# ST-BOARD-1-02.net
KiCad netlist of a schematic drawn in EAGLE
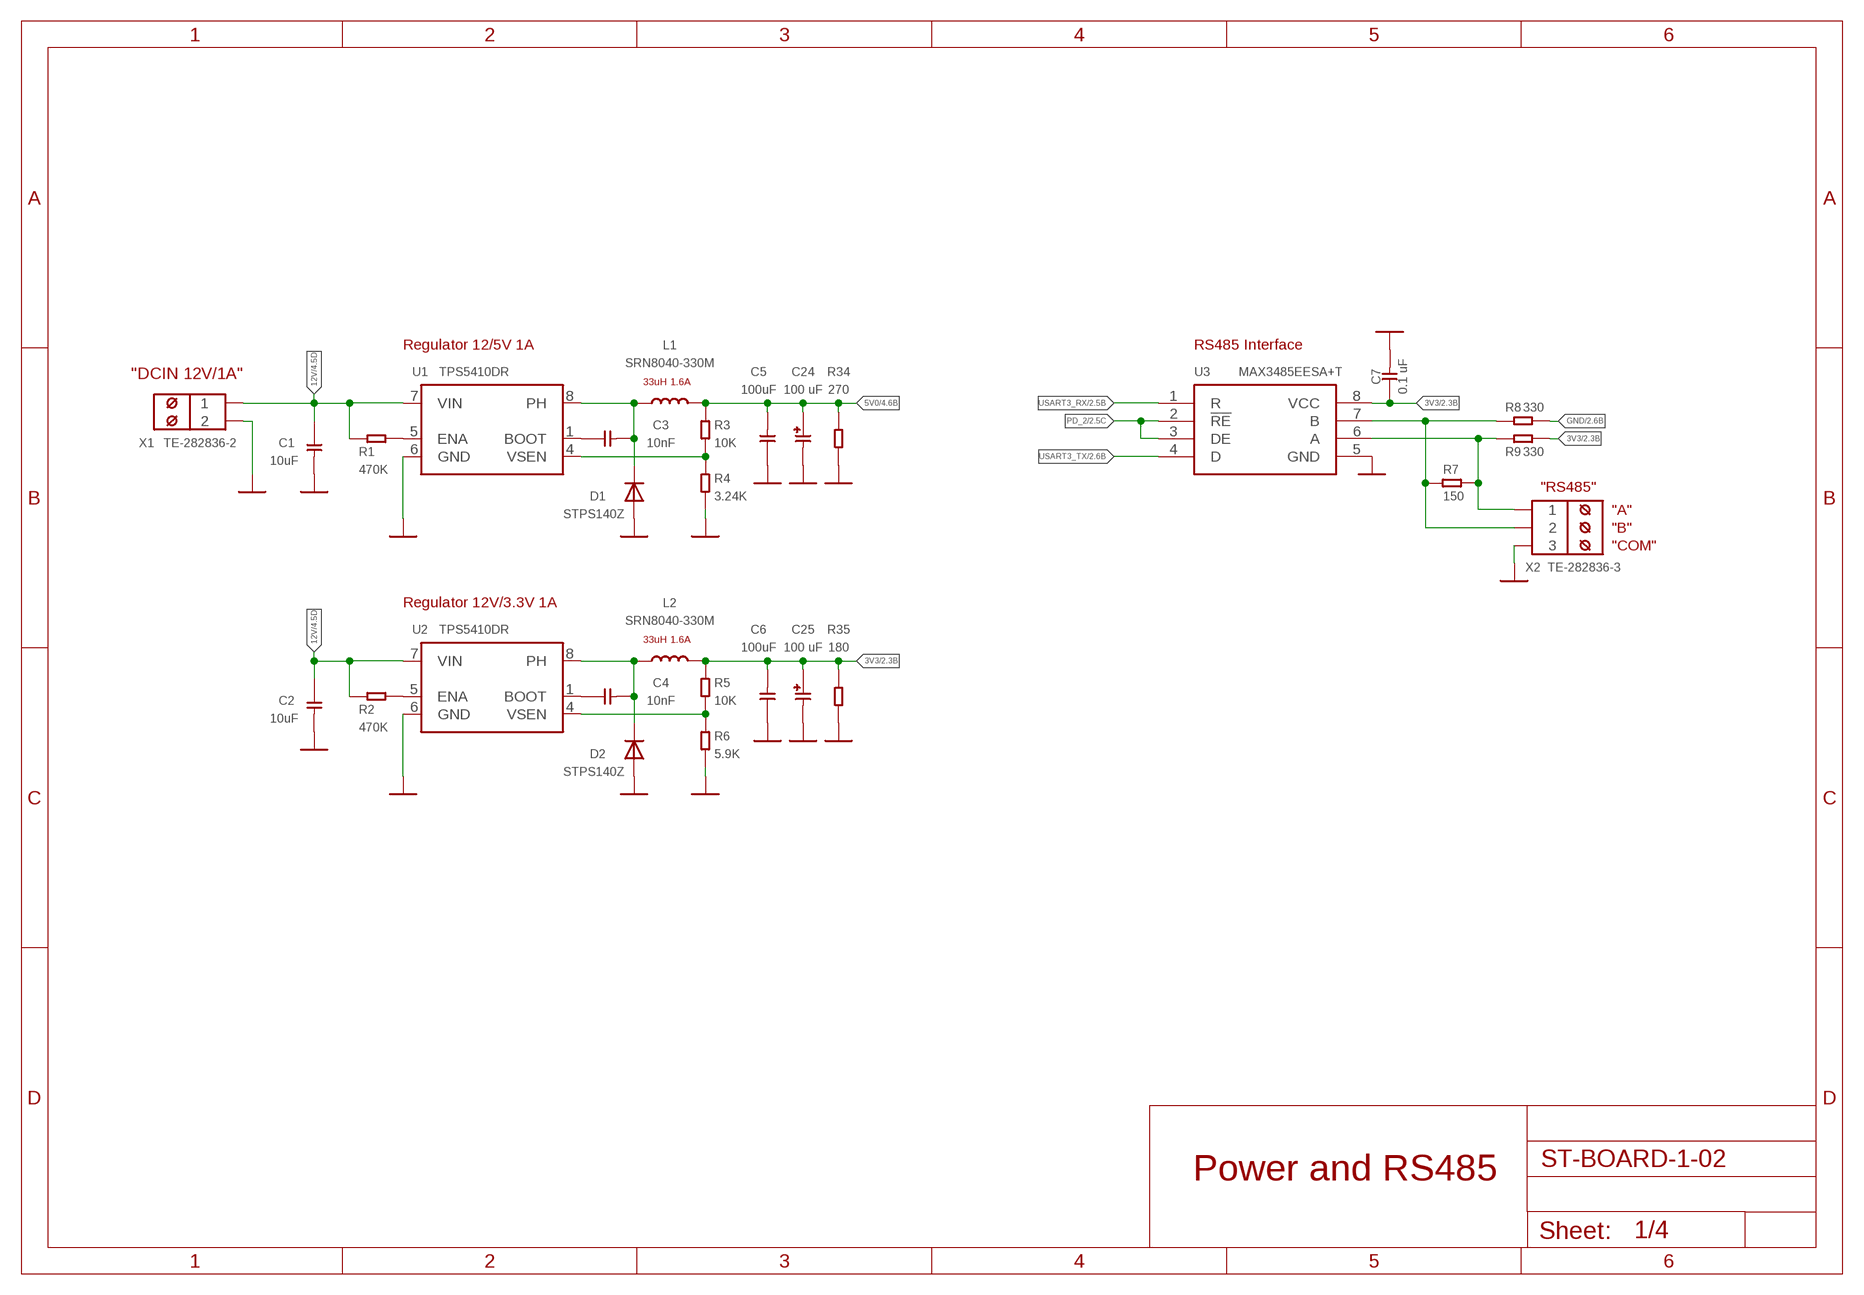
[diagram p0: schematic, sheet 1]
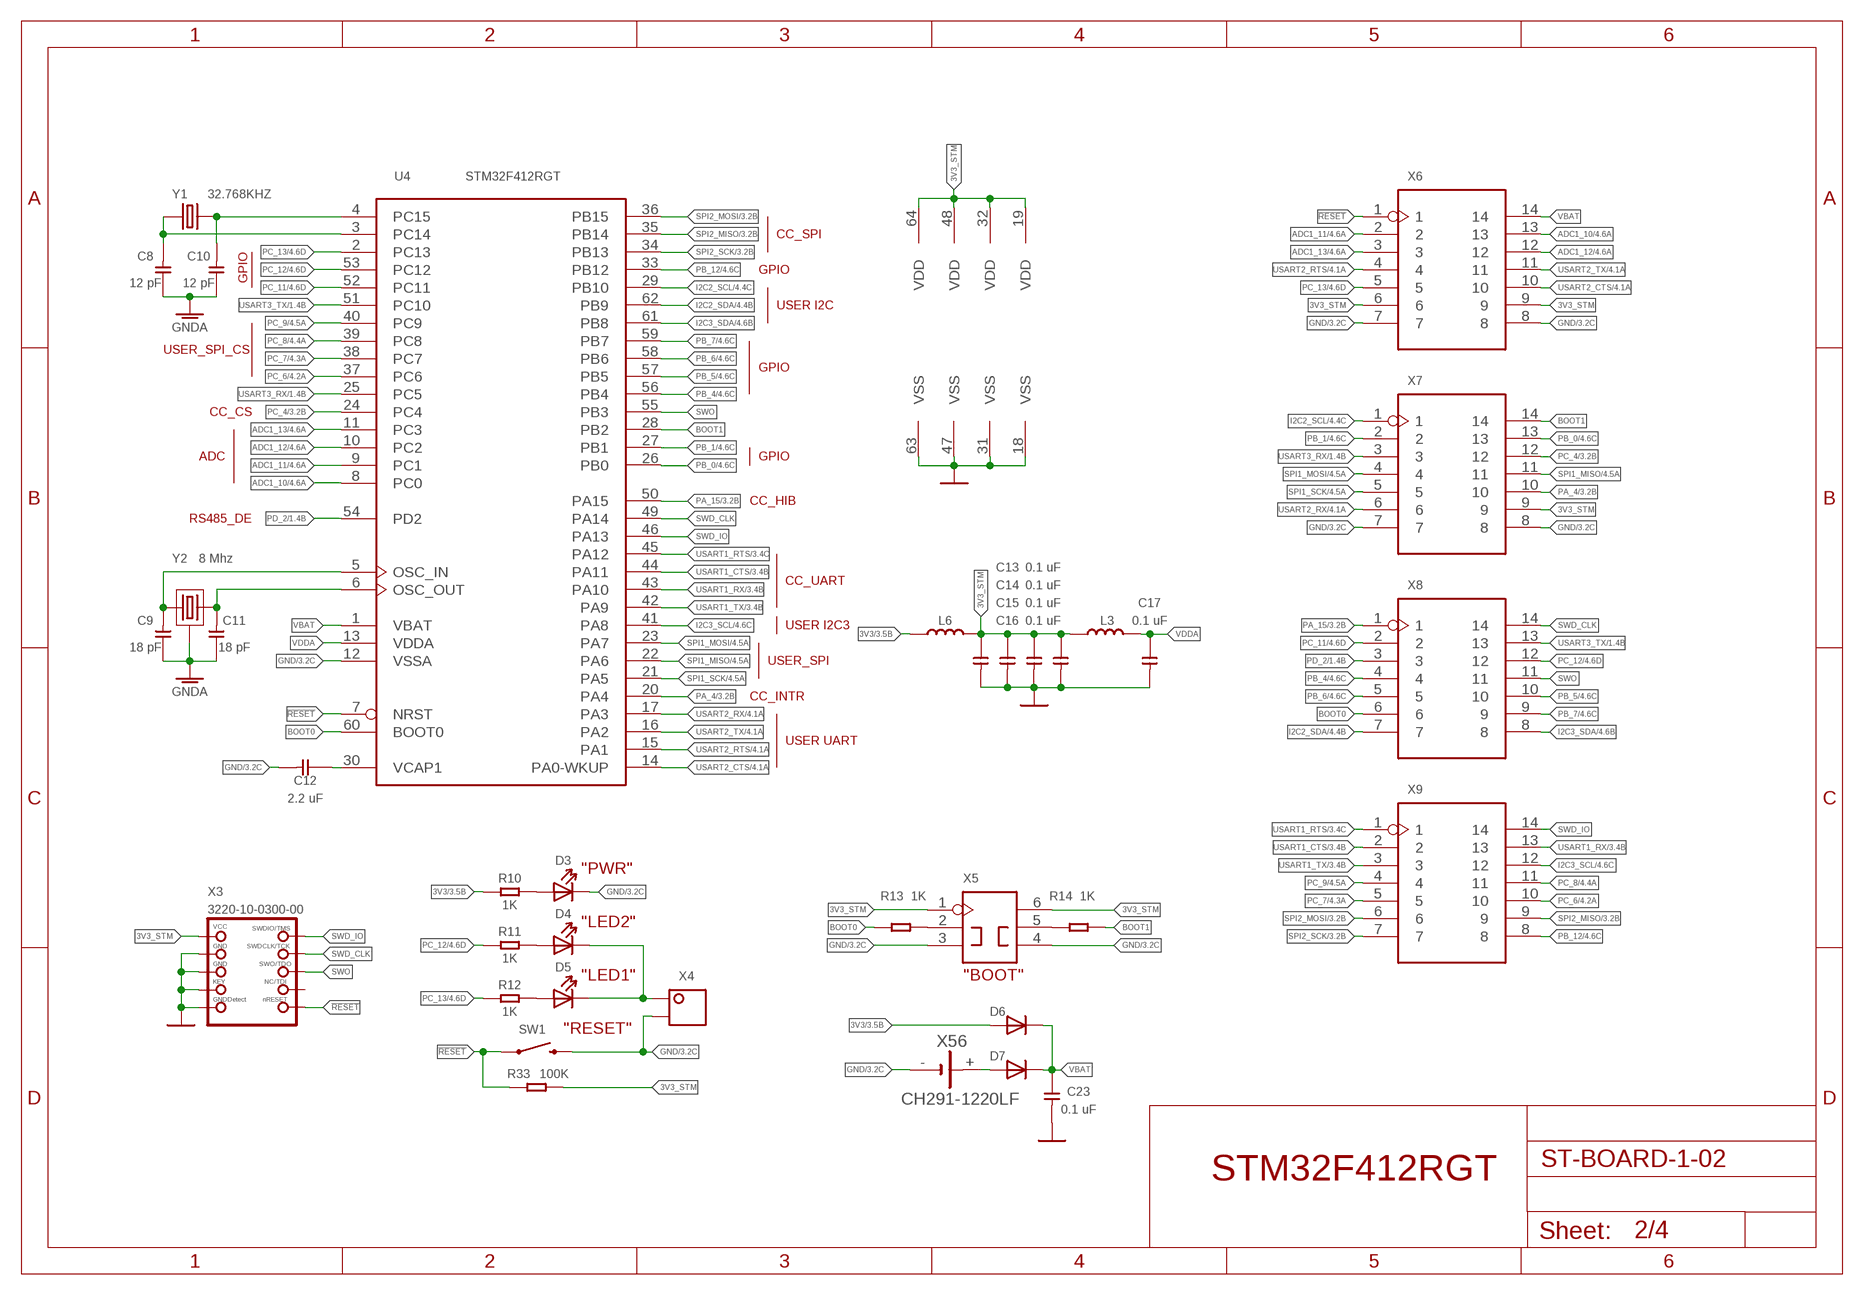
[diagram p1: schematic, sheet 2]
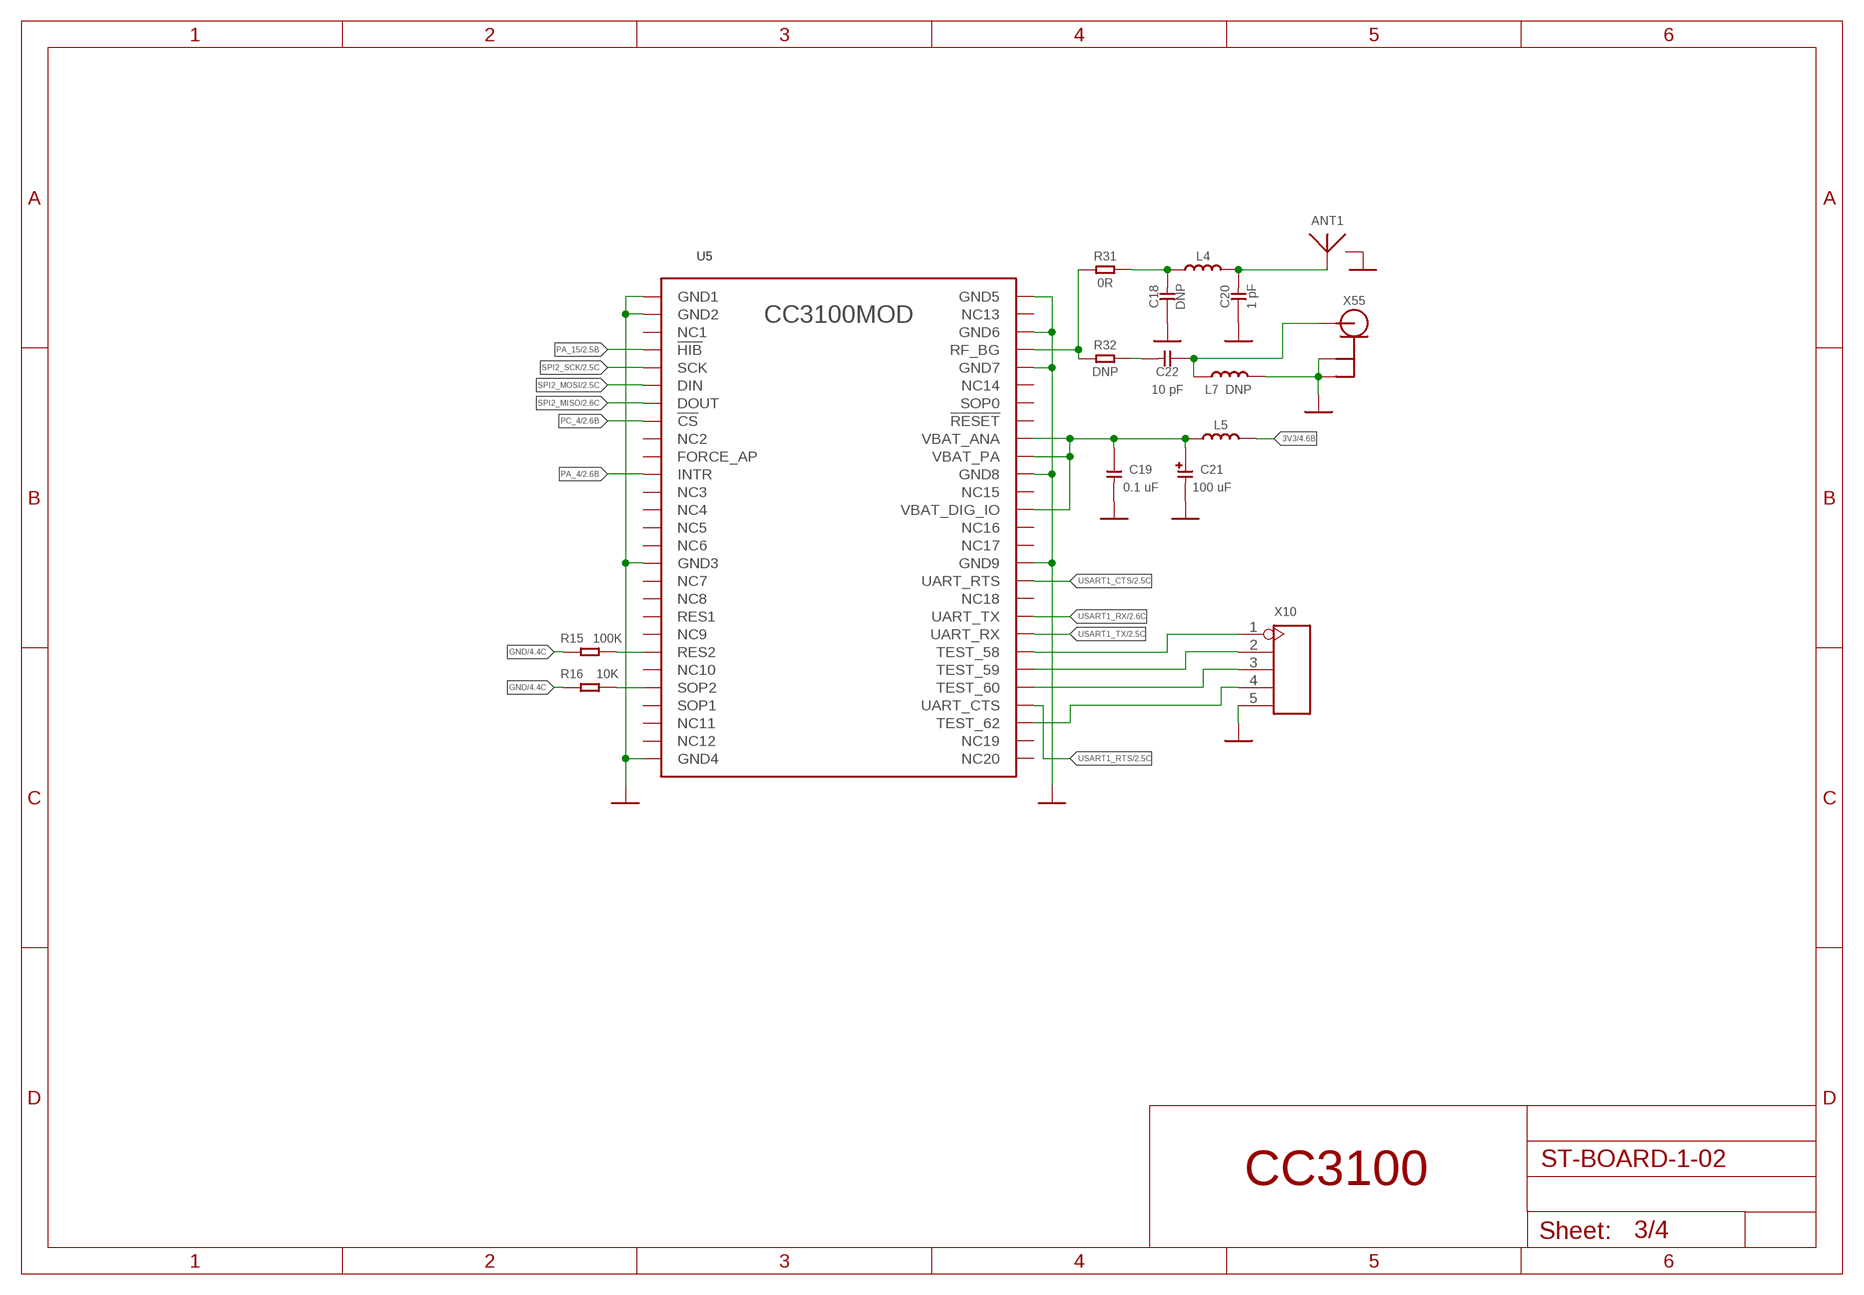
[diagram p2: schematic, sheet 3]
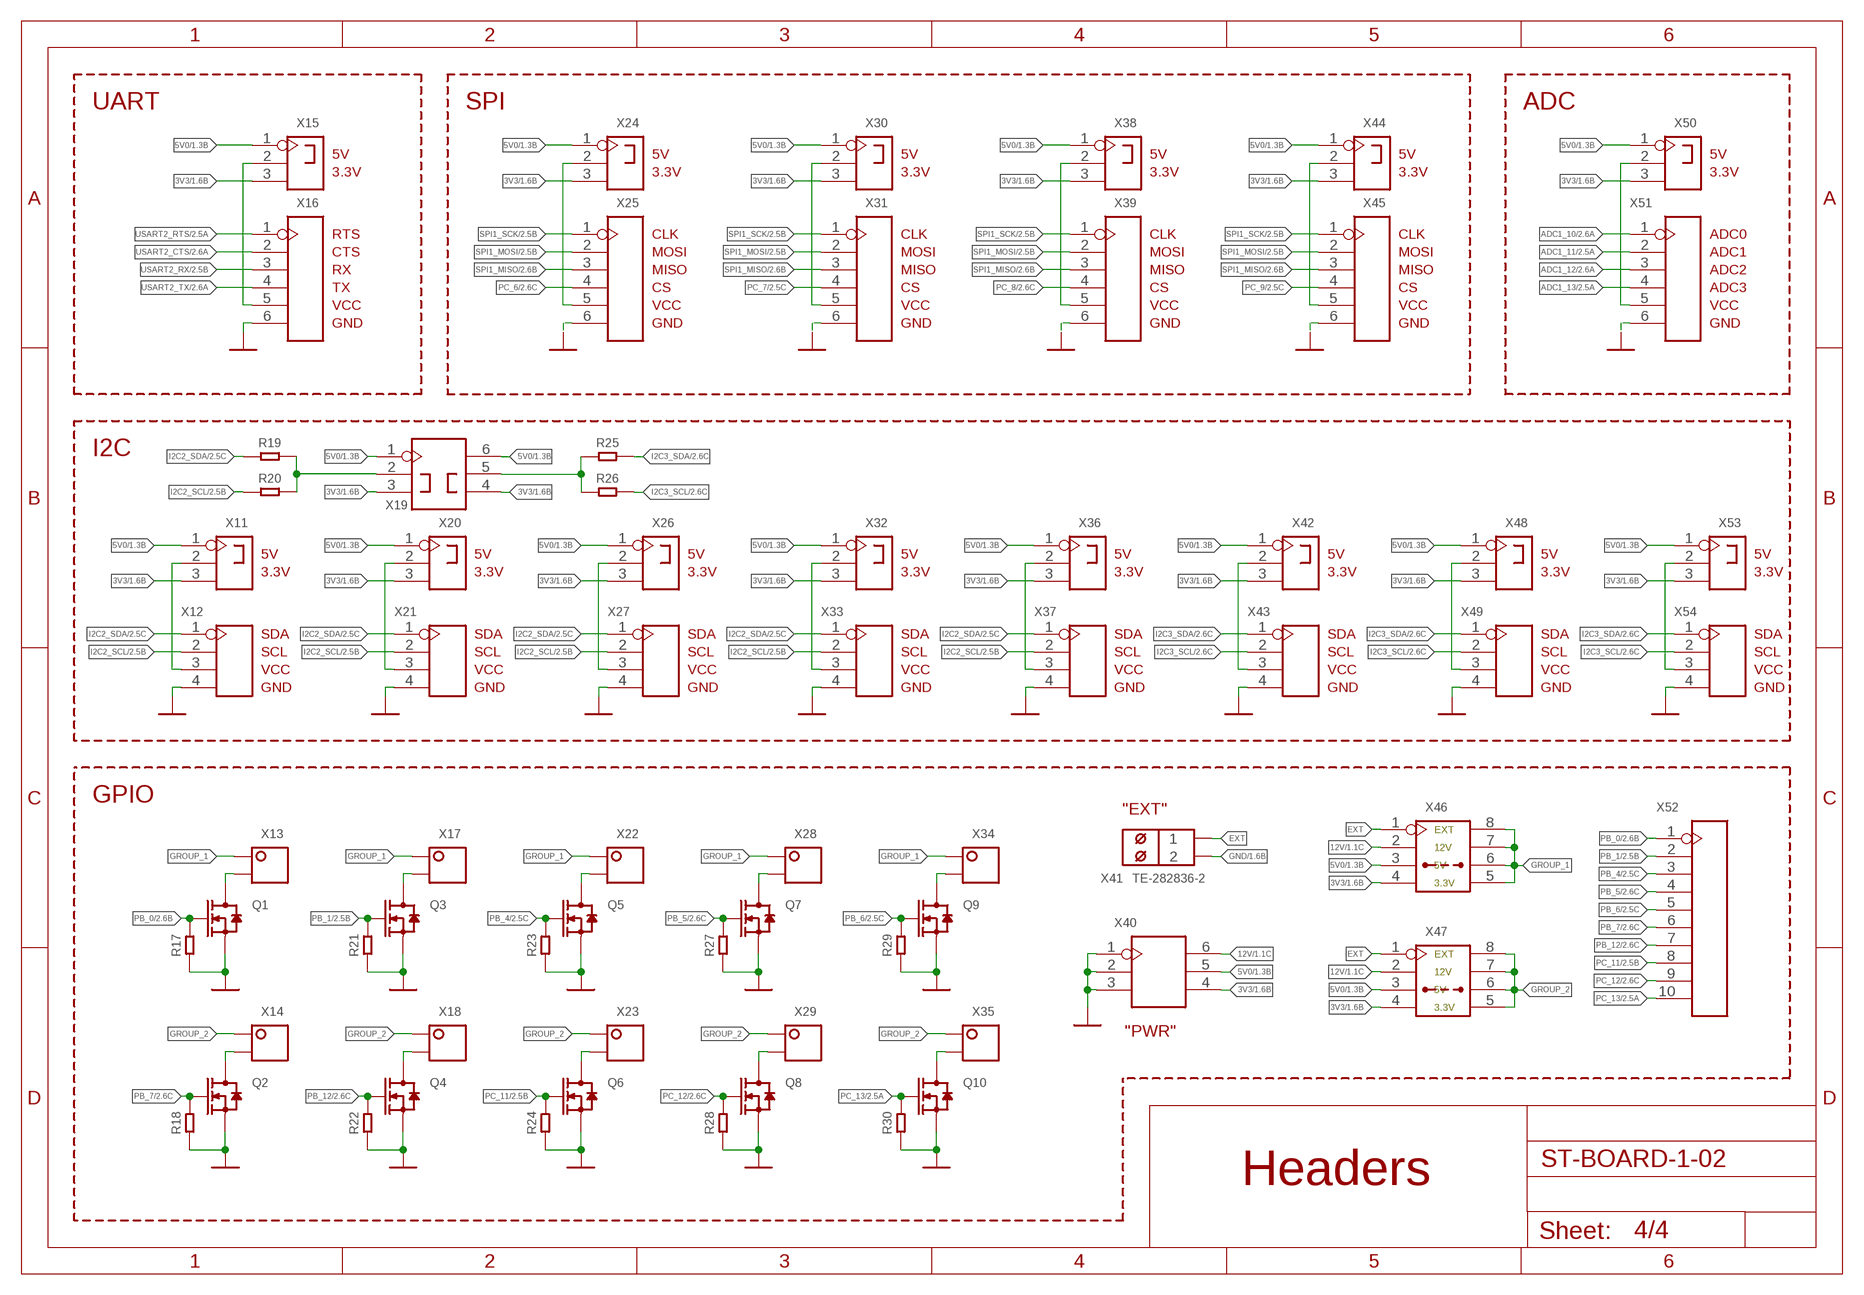
[diagram p3: schematic, sheet 4]

(export (version "E")
  (design (tool "Eeschema 10.0.6"))
  (components
    (comp (ref "Q1")
      (value "MOSFET-N-(SOT-23)")
      (footprint "eagle-import:SOT-23")
      (libsource (lib "eagle-import") (part "MOSFET-N-(SOT-23)"))
    )
    (comp (ref "Q2")
      (value "MOSFET-N-(SOT-23)")
      (footprint "eagle-import:SOT-23")
      (libsource (lib "eagle-import") (part "MOSFET-N-(SOT-23)"))
    )
    (comp (ref "Q3")
      (value "MOSFET-N-(SOT-23)")
      (footprint "eagle-import:SOT-23")
      (libsource (lib "eagle-import") (part "MOSFET-N-(SOT-23)"))
    )
    (comp (ref "Q4")
      (value "MOSFET-N-(SOT-23)")
      (footprint "eagle-import:SOT-23")
      (libsource (lib "eagle-import") (part "MOSFET-N-(SOT-23)"))
    )
    (comp (ref "Q5")
      (value "MOSFET-N-(SOT-23)")
      (footprint "eagle-import:SOT-23")
      (libsource (lib "eagle-import") (part "MOSFET-N-(SOT-23)"))
    )
    (comp (ref "Q6")
      (value "MOSFET-N-(SOT-23)")
      (footprint "eagle-import:SOT-23")
      (libsource (lib "eagle-import") (part "MOSFET-N-(SOT-23)"))
    )
    (comp (ref "Q7")
      (value "MOSFET-N-(SOT-23)")
      (footprint "eagle-import:SOT-23")
      (libsource (lib "eagle-import") (part "MOSFET-N-(SOT-23)"))
    )
    (comp (ref "Q8")
      (value "MOSFET-N-(SOT-23)")
      (footprint "eagle-import:SOT-23")
      (libsource (lib "eagle-import") (part "MOSFET-N-(SOT-23)"))
    )
    (comp (ref "Q9")
      (value "MOSFET-N-(SOT-23)")
      (footprint "eagle-import:SOT-23")
      (libsource (lib "eagle-import") (part "MOSFET-N-(SOT-23)"))
    )
    (comp (ref "Q10")
      (value "MOSFET-N-(SOT-23)")
      (footprint "eagle-import:SOT-23")
      (libsource (lib "eagle-import") (part "MOSFET-N-(SOT-23)"))
    )
    (comp (ref "R17")
      (value "CHIP-RESISTOR-0603")
      (footprint "eagle-import:R0603")
      (libsource (lib "eagle-import") (part "CHIP-RESISTOR-0603"))
    )
    (comp (ref "R18")
      (value "CHIP-RESISTOR-0603")
      (footprint "eagle-import:R0603")
      (libsource (lib "eagle-import") (part "CHIP-RESISTOR-0603"))
    )
    (comp (ref "R19")
      (value "CHIP-RESISTOR-0603")
      (footprint "eagle-import:R0603")
      (libsource (lib "eagle-import") (part "CHIP-RESISTOR-0603"))
    )
    (comp (ref "R20")
      (value "CHIP-RESISTOR-0603")
      (footprint "eagle-import:R0603")
      (libsource (lib "eagle-import") (part "CHIP-RESISTOR-0603"))
    )
    (comp (ref "R21")
      (value "CHIP-RESISTOR-0603")
      (footprint "eagle-import:R0603")
      (libsource (lib "eagle-import") (part "CHIP-RESISTOR-0603"))
    )
    (comp (ref "R22")
      (value "CHIP-RESISTOR-0603")
      (footprint "eagle-import:R0603")
      (libsource (lib "eagle-import") (part "CHIP-RESISTOR-0603"))
    )
    (comp (ref "R23")
      (value "CHIP-RESISTOR-0603")
      (footprint "eagle-import:R0603")
      (libsource (lib "eagle-import") (part "CHIP-RESISTOR-0603"))
    )
    (comp (ref "R24")
      (value "CHIP-RESISTOR-0603")
      (footprint "eagle-import:R0603")
      (libsource (lib "eagle-import") (part "CHIP-RESISTOR-0603"))
    )
    (comp (ref "R25")
      (value "CHIP-RESISTOR-0603")
      (footprint "eagle-import:R0603")
      (libsource (lib "eagle-import") (part "CHIP-RESISTOR-0603"))
    )
    (comp (ref "R26")
      (value "CHIP-RESISTOR-0603")
      (footprint "eagle-import:R0603")
      (libsource (lib "eagle-import") (part "CHIP-RESISTOR-0603"))
    )
    (comp (ref "R27")
      (value "CHIP-RESISTOR-0603")
      (footprint "eagle-import:R0603")
      (libsource (lib "eagle-import") (part "CHIP-RESISTOR-0603"))
    )
    (comp (ref "R28")
      (value "CHIP-RESISTOR-0603")
      (footprint "eagle-import:R0603")
      (libsource (lib "eagle-import") (part "CHIP-RESISTOR-0603"))
    )
    (comp (ref "R29")
      (value "CHIP-RESISTOR-0603")
      (footprint "eagle-import:R0603")
      (libsource (lib "eagle-import") (part "CHIP-RESISTOR-0603"))
    )
    (comp (ref "R30")
      (value "CHIP-RESISTOR-0603")
      (footprint "eagle-import:R0603")
      (libsource (lib "eagle-import") (part "CHIP-RESISTOR-0603"))
    )
    (comp (ref "X11")
      (value "3p-2.54")
      (footprint "eagle-import:H3-2.54")
      (fields (field (name "MPN") "F185-1103A0BSYA1"))
      (libsource (lib "eagle-import") (part "DIP-HEADER-VERT(3P-2.54)_M"))
    )
    (comp (ref "X12")
      (value "DIP-HEADER-VERT(4P-2.54)_WF")
      (footprint "eagle-import:22-23-2041")
      (libsource (lib "eagle-import") (part "DIP-HEADER-VERT(4P-2.54)_WF"))
    )
    (comp (ref "X13")
      (value "2p-2.54")
      (footprint "eagle-import:22-23-2021")
      (libsource (lib "eagle-import") (part "DIP-HEADER-VERT(2P-2.54)_WF"))
    )
    (comp (ref "X14")
      (value "2p-2.54")
      (footprint "eagle-import:22-23-2021")
      (libsource (lib "eagle-import") (part "DIP-HEADER-VERT(2P-2.54)_WF"))
    )
    (comp (ref "X15")
      (value "3p-2.54")
      (footprint "eagle-import:H3-2.54")
      (fields (field (name "MPN") "F185-1103A0BSYA1"))
      (libsource (lib "eagle-import") (part "DIP-HEADER-VERT(3P-2.54)_M"))
    )
    (comp (ref "X16")
      (value "DIP-HEADER-VERT(6P-2.54)_WF")
      (footprint "eagle-import:22-23-2061")
      (libsource (lib "eagle-import") (part "DIP-HEADER-VERT(6P-2.54)_WF"))
    )
    (comp (ref "X17")
      (value "2p-2.54")
      (footprint "eagle-import:22-23-2021")
      (libsource (lib "eagle-import") (part "DIP-HEADER-VERT(2P-2.54)_WF"))
    )
    (comp (ref "X18")
      (value "2p-2.54")
      (footprint "eagle-import:22-23-2021")
      (libsource (lib "eagle-import") (part "DIP-HEADER-VERT(2P-2.54)_WF"))
    )
    (comp (ref "X19")
      (value "2x3p-2.54")
      (footprint "eagle-import:H2X3-2.54")
      (fields (field (name "MPN") "P125-12A1BS116A1"))
      (libsource (lib "eagle-import") (part "DIP-HEADER-VERT(2X3P-2.54）-2.54"))
    )
    (comp (ref "X20")
      (value "3p-2.54")
      (footprint "eagle-import:H3-2.54")
      (fields (field (name "MPN") "F185-1103A0BSYA1"))
      (libsource (lib "eagle-import") (part "DIP-HEADER-VERT(3P-2.54)_M"))
    )
    (comp (ref "X21")
      (value "DIP-HEADER-VERT(4P-2.54)_WF")
      (footprint "eagle-import:22-23-2041")
      (libsource (lib "eagle-import") (part "DIP-HEADER-VERT(4P-2.54)_WF"))
    )
    (comp (ref "X22")
      (value "2p-2.54")
      (footprint "eagle-import:22-23-2021")
      (libsource (lib "eagle-import") (part "DIP-HEADER-VERT(2P-2.54)_WF"))
    )
    (comp (ref "X23")
      (value "2p-2.54")
      (footprint "eagle-import:22-23-2021")
      (libsource (lib "eagle-import") (part "DIP-HEADER-VERT(2P-2.54)_WF"))
    )
    (comp (ref "X24")
      (value "3p-2.54")
      (footprint "eagle-import:H3-2.54")
      (fields (field (name "MPN") "F185-1103A0BSYA1"))
      (libsource (lib "eagle-import") (part "DIP-HEADER-VERT(3P-2.54)_M"))
    )
    (comp (ref "X25")
      (value "DIP-HEADER-VERT(6P-2.54)_WF")
      (footprint "eagle-import:22-23-2061")
      (libsource (lib "eagle-import") (part "DIP-HEADER-VERT(6P-2.54)_WF"))
    )
    (comp (ref "X26")
      (value "3p-2.54")
      (footprint "eagle-import:H3-2.54")
      (fields (field (name "MPN") "F185-1103A0BSYA1"))
      (libsource (lib "eagle-import") (part "DIP-HEADER-VERT(3P-2.54)_M"))
    )
    (comp (ref "X27")
      (value "DIP-HEADER-VERT(4P-2.54)_WF")
      (footprint "eagle-import:22-23-2041")
      (libsource (lib "eagle-import") (part "DIP-HEADER-VERT(4P-2.54)_WF"))
    )
    (comp (ref "X28")
      (value "2p-2.54")
      (footprint "eagle-import:22-23-2021")
      (libsource (lib "eagle-import") (part "DIP-HEADER-VERT(2P-2.54)_WF"))
    )
    (comp (ref "X29")
      (value "2p-2.54")
      (footprint "eagle-import:22-23-2021")
      (libsource (lib "eagle-import") (part "DIP-HEADER-VERT(2P-2.54)_WF"))
    )
    (comp (ref "X30")
      (value "3p-2.54")
      (footprint "eagle-import:H3-2.54")
      (fields (field (name "MPN") "F185-1103A0BSYA1"))
      (libsource (lib "eagle-import") (part "DIP-HEADER-VERT(3P-2.54)_M"))
    )
    (comp (ref "X31")
      (value "DIP-HEADER-VERT(6P-2.54)_WF")
      (footprint "eagle-import:22-23-2061")
      (libsource (lib "eagle-import") (part "DIP-HEADER-VERT(6P-2.54)_WF"))
    )
    (comp (ref "X32")
      (value "3p-2.54")
      (footprint "eagle-import:H3-2.54")
      (fields (field (name "MPN") "F185-1103A0BSYA1"))
      (libsource (lib "eagle-import") (part "DIP-HEADER-VERT(3P-2.54)_M"))
    )
    (comp (ref "X33")
      (value "DIP-HEADER-VERT(4P-2.54)_WF")
      (footprint "eagle-import:22-23-2041")
      (libsource (lib "eagle-import") (part "DIP-HEADER-VERT(4P-2.54)_WF"))
    )
    (comp (ref "X34")
      (value "2p-2.54")
      (footprint "eagle-import:22-23-2021")
      (libsource (lib "eagle-import") (part "DIP-HEADER-VERT(2P-2.54)_WF"))
    )
    (comp (ref "X35")
      (value "2p-2.54")
      (footprint "eagle-import:22-23-2021")
      (libsource (lib "eagle-import") (part "DIP-HEADER-VERT(2P-2.54)_WF"))
    )
    (comp (ref "X36")
      (value "3p-2.54")
      (footprint "eagle-import:H3-2.54")
      (fields (field (name "MPN") "F185-1103A0BSYA1"))
      (libsource (lib "eagle-import") (part "DIP-HEADER-VERT(3P-2.54)_M"))
    )
    (comp (ref "X37")
      (value "DIP-HEADER-VERT(4P-2.54)_WF")
      (footprint "eagle-import:22-23-2041")
      (libsource (lib "eagle-import") (part "DIP-HEADER-VERT(4P-2.54)_WF"))
    )
    (comp (ref "X38")
      (value "3p-2.54")
      (footprint "eagle-import:H3-2.54")
      (fields (field (name "MPN") "F185-1103A0BSYA1"))
      (libsource (lib "eagle-import") (part "DIP-HEADER-VERT(3P-2.54)_M"))
    )
    (comp (ref "X39")
      (value "DIP-HEADER-VERT(6P-2.54)_WF")
      (footprint "eagle-import:22-23-2061")
      (libsource (lib "eagle-import") (part "DIP-HEADER-VERT(6P-2.54)_WF"))
    )
    (comp (ref "X40")
      (value "2x3p-2.54")
      (footprint "eagle-import:H2X3-2.54")
      (fields (field (name "MPN") "P125-12A1BS116A1"))
      (libsource (lib "eagle-import") (part "DIP-HEADER-VERT(2X3P-2.54）-2.54"))
    )
    (comp (ref "X41")
      (value "TE-282836-2")
      (footprint "eagle-import:W237-102")
      (libsource (lib "eagle-import") (part "TE-282836-2"))
    )
    (comp (ref "X42")
      (value "3p-2.54")
      (footprint "eagle-import:H3-2.54")
      (fields (field (name "MPN") "F185-1103A0BSYA1"))
      (libsource (lib "eagle-import") (part "DIP-HEADER-VERT(3P-2.54)_M"))
    )
    (comp (ref "X43")
      (value "DIP-HEADER-VERT(4P-2.54)_WF")
      (footprint "eagle-import:22-23-2041")
      (libsource (lib "eagle-import") (part "DIP-HEADER-VERT(4P-2.54)_WF"))
    )
    (comp (ref "X44")
      (value "3p-2.54")
      (footprint "eagle-import:H3-2.54")
      (fields (field (name "MPN") "F185-1103A0BSYA1"))
      (libsource (lib "eagle-import") (part "DIP-HEADER-VERT(3P-2.54)_M"))
    )
    (comp (ref "X45")
      (value "DIP-HEADER-VERT(6P-2.54)_WF")
      (footprint "eagle-import:22-23-2061")
      (libsource (lib "eagle-import") (part "DIP-HEADER-VERT(6P-2.54)_WF"))
    )
    (comp (ref "X46")
      (value "2x4p-2.54")
      (footprint "eagle-import:H2X4-2.54")
      (fields (field (name "MPN") "P125-1208A0BS116A2"))
      (libsource (lib "eagle-import") (part "DIP-HEADER-VERT(2X4P-2.54)"))
    )
    (comp (ref "X47")
      (value "2x4p-2.54")
      (footprint "eagle-import:H2X4-2.54")
      (fields (field (name "MPN") "P125-1208A0BS116A2"))
      (libsource (lib "eagle-import") (part "DIP-HEADER-VERT(2X4P-2.54)"))
    )
    (comp (ref "X48")
      (value "3p-2.54")
      (footprint "eagle-import:H3-2.54")
      (fields (field (name "MPN") "F185-1103A0BSYA1"))
      (libsource (lib "eagle-import") (part "DIP-HEADER-VERT(3P-2.54)_M"))
    )
    (comp (ref "X49")
      (value "DIP-HEADER-VERT(4P-2.54)_WF")
      (footprint "eagle-import:22-23-2041")
      (libsource (lib "eagle-import") (part "DIP-HEADER-VERT(4P-2.54)_WF"))
    )
    (comp (ref "X50")
      (value "3p-2.54")
      (footprint "eagle-import:H3-2.54")
      (fields (field (name "MPN") "F185-1103A0BSYA1"))
      (libsource (lib "eagle-import") (part "DIP-HEADER-VERT(3P-2.54)_M"))
    )
    (comp (ref "X51")
      (value "DIP-HEADER-VERT(6P-2.54)")
      (footprint "eagle-import:H6-2.54")
      (libsource (lib "eagle-import") (part "DIP-HEADER-VERT(6P-2.54)"))
    )
    (comp (ref "X52")
      (value "DIP-HEADER-VERT(10P-2.54)")
      (footprint "eagle-import:H10-2.54")
      (libsource (lib "eagle-import") (part "DIP-HEADER-VERT(10P-2.54)"))
    )
    (comp (ref "X53")
      (value "3p-2.54")
      (footprint "eagle-import:H3-2.54")
      (fields (field (name "MPN") "F185-1103A0BSYA1"))
      (libsource (lib "eagle-import") (part "DIP-HEADER-VERT(3P-2.54)_M"))
    )
    (comp (ref "X54")
      (value "DIP-HEADER-VERT(4P-2.54)_WF")
      (footprint "eagle-import:22-23-2041")
      (libsource (lib "eagle-import") (part "DIP-HEADER-VERT(4P-2.54)_WF"))
    )
    (comp (ref "ANT1")
      (value "AH316M245001-T")
      (footprint "eagle-import:AH316M")
      (libsource (lib "eagle-import") (part "AH316M"))
    )
    (comp (ref "C18")
      (value "DNP")
      (footprint "eagle-import:C0402")
      (libsource (lib "eagle-import") (part "CHIP-CAPACITORC0402"))
    )
    (comp (ref "C19")
      (value "0.1 uF")
      (footprint "eagle-import:C0603")
      (libsource (lib "eagle-import") (part "CHIP-CAPACITORC0603"))
    )
    (comp (ref "C20")
      (value "1 pF")
      (footprint "eagle-import:C0402")
      (libsource (lib "eagle-import") (part "CHIP-CAPACITORC0402"))
    )
    (comp (ref "C21")
      (value "100 uF")
      (footprint "eagle-import:CT3528")
      (libsource (lib "eagle-import") (part "TANT-CAPACITOR_B"))
    )
    (comp (ref "C22")
      (value "10 pF")
      (footprint "eagle-import:C0402")
      (libsource (lib "eagle-import") (part "CHIP-CAPACITORC0402"))
    )
    (comp (ref "L4")
      (value "CHIP-INDUCTOR_L0402")
      (footprint "eagle-import:L0402")
      (libsource (lib "eagle-import") (part "CHIP-INDUCTOR_L0402"))
    )
    (comp (ref "L5")
      (value "CHIP-INDUCTOR_L0603")
      (footprint "eagle-import:L0603")
      (libsource (lib "eagle-import") (part "CHIP-INDUCTOR_L0603"))
    )
    (comp (ref "L7")
      (value "DNP")
      (footprint "eagle-import:L0402")
      (libsource (lib "eagle-import") (part "CHIP-INDUCTOR_L0402"))
    )
    (comp (ref "R15")
      (value "100K")
      (footprint "eagle-import:R0603")
      (libsource (lib "eagle-import") (part "CHIP-RESISTOR-0603"))
    )
    (comp (ref "R16")
      (value "10K")
      (footprint "eagle-import:R0603")
      (libsource (lib "eagle-import") (part "CHIP-RESISTOR-0603"))
    )
    (comp (ref "R31")
      (value "0R")
      (footprint "eagle-import:R0402")
      (libsource (lib "eagle-import") (part "CHIP-RESISTOR-0402"))
    )
    (comp (ref "R32")
      (value "DNP")
      (footprint "eagle-import:R0402")
      (libsource (lib "eagle-import") (part "CHIP-RESISTOR-0402"))
    )
    (comp (ref "U5")
      (value "CC3100MOD")
      (footprint "eagle-import:CC3100MOD")
      (libsource (lib "eagle-import") (part "CC3100MOD"))
    )
    (comp (ref "X10")
      (value "2p-2.54")
      (footprint "eagle-import:H5-2.54")
      (libsource (lib "eagle-import") (part "DIP-HEADER-VERT(5P-2.54)"))
    )
    (comp (ref "X55")
      (value "UFL3")
      (footprint "eagle-import:U-FL3P-SMD-2.6X2.6X1.0MM")
      (libsource (lib "eagle-import") (part "UFL3"))
    )
    (comp (ref "C8")
      (value "12 pF")
      (footprint "eagle-import:C0603")
      (libsource (lib "eagle-import") (part "CHIP-CAPACITORC0603"))
    )
    (comp (ref "C9")
      (value "18 pF")
      (footprint "eagle-import:C0603")
      (libsource (lib "eagle-import") (part "CHIP-CAPACITORC0603"))
    )
    (comp (ref "C10")
      (value "12 pF")
      (footprint "eagle-import:C0603")
      (libsource (lib "eagle-import") (part "CHIP-CAPACITORC0603"))
    )
    (comp (ref "C11")
      (value "18 pF")
      (footprint "eagle-import:C0603")
      (libsource (lib "eagle-import") (part "CHIP-CAPACITORC0603"))
    )
    (comp (ref "C12")
      (value "2.2 uF")
      (footprint "eagle-import:C0603")
      (libsource (lib "eagle-import") (part "CHIP-CAPACITORC0603"))
    )
    (comp (ref "C13")
      (value "0.1 uF")
      (footprint "eagle-import:C0603")
      (libsource (lib "eagle-import") (part "CHIP-CAPACITORC0603"))
    )
    (comp (ref "C14")
      (value "0.1 uF")
      (footprint "eagle-import:C0603")
      (libsource (lib "eagle-import") (part "CHIP-CAPACITORC0603"))
    )
    (comp (ref "C15")
      (value "0.1 uF")
      (footprint "eagle-import:C0603")
      (libsource (lib "eagle-import") (part "CHIP-CAPACITORC0603"))
    )
    (comp (ref "C16")
      (value "0.1 uF")
      (footprint "eagle-import:C0603")
      (libsource (lib "eagle-import") (part "CHIP-CAPACITORC0603"))
    )
    (comp (ref "C17")
      (value "0.1 uF")
      (footprint "eagle-import:C0603")
      (libsource (lib "eagle-import") (part "CHIP-CAPACITORC0603"))
    )
    (comp (ref "C23")
      (value "0.1 uF")
      (footprint "eagle-import:C0603")
      (libsource (lib "eagle-import") (part "CHIP-CAPACITORC0603"))
    )
    (comp (ref "D3")
      (value "LED-0603")
      (footprint "eagle-import:LED-0603")
      (libsource (lib "eagle-import") (part "LED-0603"))
    )
    (comp (ref "D4")
      (value "LED-0603")
      (footprint "eagle-import:LED-0603")
      (libsource (lib "eagle-import") (part "LED-0603"))
    )
    (comp (ref "D5")
      (value "LED-0603")
      (footprint "eagle-import:LED-0603")
      (libsource (lib "eagle-import") (part "LED-0603"))
    )
    (comp (ref "D6")
      (value "DIODE_SOD-523")
      (footprint "eagle-import:SOD-523")
      (libsource (lib "eagle-import") (part "DIODE_SOD-523"))
    )
    (comp (ref "D7")
      (value "DIODE_SOD-523")
      (footprint "eagle-import:SOD-523")
      (libsource (lib "eagle-import") (part "DIODE_SOD-523"))
    )
    (comp (ref "L3")
      (value "CHIP-INDUCTOR_L0603")
      (footprint "eagle-import:L0603")
      (libsource (lib "eagle-import") (part "CHIP-INDUCTOR_L0603"))
    )
    (comp (ref "L6")
      (value "CHIP-INDUCTOR_L0603")
      (footprint "eagle-import:L0603")
      (libsource (lib "eagle-import") (part "CHIP-INDUCTOR_L0603"))
    )
    (comp (ref "R10")
      (value "1K")
      (footprint "eagle-import:R0603")
      (libsource (lib "eagle-import") (part "CHIP-RESISTOR-0603"))
    )
    (comp (ref "R11")
      (value "1K")
      (footprint "eagle-import:R0603")
      (libsource (lib "eagle-import") (part "CHIP-RESISTOR-0603"))
    )
    (comp (ref "R12")
      (value "1K")
      (footprint "eagle-import:R0603")
      (libsource (lib "eagle-import") (part "CHIP-RESISTOR-0603"))
    )
    (comp (ref "R13")
      (value "1K")
      (footprint "eagle-import:R0603")
      (libsource (lib "eagle-import") (part "CHIP-RESISTOR-0603"))
    )
    (comp (ref "R14")
      (value "1K")
      (footprint "eagle-import:R0603")
      (libsource (lib "eagle-import") (part "CHIP-RESISTOR-0603"))
    )
    (comp (ref "R33")
      (value "100K")
      (footprint "eagle-import:R0603")
      (libsource (lib "eagle-import") (part "CHIP-RESISTOR-0603"))
    )
    (comp (ref "SW1")
      (value "TE-1437566-3")
      (footprint "eagle-import:TE-1437566-3")
      (libsource (lib "eagle-import") (part "TE-1437566-3"))
    )
    (comp (ref "U4")
      (value "STM32F412RGT")
      (footprint "eagle-import:LQFP64")
      (libsource (lib "eagle-import") (part "STM32F412RTG"))
    )
    (comp (ref "X3")
      (value "3220-10-0300-00")
      (footprint "eagle-import:2X05_1.27MM_BOX_NOPOSTS")
      (libsource (lib "eagle-import") (part "JTAG-CORTEXBOX"))
    )
    (comp (ref "X4")
      (value "2p-2.54")
      (footprint "eagle-import:H2-2.54")
      (fields (field (name "MPN") "F185-1102A1BSYA1"))
      (libsource (lib "eagle-import") (part "DIP-HEADER-VERT(2P-2.54)"))
    )
    (comp (ref "X5")
      (value "2x3p-2.54")
      (footprint "eagle-import:H2X3-2.54")
      (fields (field (name "MPN") "P125-12A1BS116A1"))
      (libsource (lib "eagle-import") (part "DIP-HEADER-VERT(2X3P-2.54）-2.54"))
    )
    (comp (ref "X6")
      (value "DIP-HEADER-VERT(2X7P-2.54)")
      (footprint "eagle-import:H2X7-2.54")
      (libsource (lib "eagle-import") (part "DIP-HEADER-VERT(2X7P-2.54)"))
    )
    (comp (ref "X7")
      (value "DIP-HEADER-VERT(2X7P-2.54)")
      (footprint "eagle-import:H2X7-2.54")
      (libsource (lib "eagle-import") (part "DIP-HEADER-VERT(2X7P-2.54)"))
    )
    (comp (ref "X8")
      (value "DIP-HEADER-VERT(2X7P-2.54)")
      (footprint "eagle-import:H2X7-2.54")
      (libsource (lib "eagle-import") (part "DIP-HEADER-VERT(2X7P-2.54)"))
    )
    (comp (ref "X9")
      (value "DIP-HEADER-VERT(2X7P-2.54)")
      (footprint "eagle-import:H2X7-2.54")
      (libsource (lib "eagle-import") (part "DIP-HEADER-VERT(2X7P-2.54)"))
    )
    (comp (ref "X56")
      (value "CH291-1220LF")
      (footprint "eagle-import:CH291-1220LF")
      (libsource (lib "eagle-import") (part "CH291-1220LF"))
    )
    (comp (ref "Y1")
      (value "32.768KHZ")
      (footprint "eagle-import:3.2X1.5")
      (fields (field (name "MPN") "FC-135") (field (name "MPN_1") "KX-327NHT 32.768 kHz GEYER"))
      (libsource (lib "eagle-import") (part "SMD-CRYSTAL_32X15"))
    )
    (comp (ref "Y2")
      (value "8 Mhz")
      (footprint "eagle-import:IQG5032B")
      (libsource (lib "eagle-import") (part "SMD-CRYSTAL-3225_5032B"))
    )
    (comp (ref "C1")
      (value "10uF")
      (footprint "eagle-import:C1206")
      (libsource (lib "eagle-import") (part "CHIP-CAPACITORC1206"))
    )
    (comp (ref "C2")
      (value "10uF")
      (footprint "eagle-import:C1206")
      (libsource (lib "eagle-import") (part "CHIP-CAPACITORC1206"))
    )
    (comp (ref "C3")
      (value "10nF")
      (footprint "eagle-import:C0603")
      (libsource (lib "eagle-import") (part "CHIP-CAPACITORC0603"))
    )
    (comp (ref "C4")
      (value "10nF")
      (footprint "eagle-import:C0603")
      (libsource (lib "eagle-import") (part "CHIP-CAPACITORC0603"))
    )
    (comp (ref "C5")
      (value "100uF")
      (footprint "eagle-import:C1206")
      (libsource (lib "eagle-import") (part "CHIP-CAPACITORC1206"))
    )
    (comp (ref "C6")
      (value "100uF")
      (footprint "eagle-import:C1206")
      (libsource (lib "eagle-import") (part "CHIP-CAPACITORC1206"))
    )
    (comp (ref "C7")
      (value "0.1 uF")
      (footprint "eagle-import:C0603")
      (libsource (lib "eagle-import") (part "CHIP-CAPACITORC0603"))
    )
    (comp (ref "C24")
      (value "100 uF")
      (footprint "eagle-import:CT7343")
      (libsource (lib "eagle-import") (part "TANT-CAPACITOR_D"))
    )
    (comp (ref "C25")
      (value "100 uF")
      (footprint "eagle-import:CT7343")
      (libsource (lib "eagle-import") (part "TANT-CAPACITOR_D"))
    )
    (comp (ref "D1")
      (value "STPS140Z")
      (footprint "eagle-import:SOD-123")
      (libsource (lib "eagle-import") (part "DIODE_SOD-123"))
    )
    (comp (ref "D2")
      (value "STPS140Z")
      (footprint "eagle-import:SOD-123")
      (libsource (lib "eagle-import") (part "DIODE_SOD-123"))
    )
    (comp (ref "L1")
      (value "SRN8040-330M")
      (footprint "eagle-import:SRN8040")
      (libsource (lib "eagle-import") (part "CHIP-INDUCTOR_SRN8040"))
    )
    (comp (ref "L2")
      (value "SRN8040-330M")
      (footprint "eagle-import:SRN8040")
      (libsource (lib "eagle-import") (part "CHIP-INDUCTOR_SRN8040"))
    )
    (comp (ref "R1")
      (value "470K")
      (footprint "eagle-import:R0603")
      (libsource (lib "eagle-import") (part "CHIP-RESISTOR-0603"))
    )
    (comp (ref "R2")
      (value "470K")
      (footprint "eagle-import:R0603")
      (libsource (lib "eagle-import") (part "CHIP-RESISTOR-0603"))
    )
    (comp (ref "R3")
      (value "10K")
      (footprint "eagle-import:R0603")
      (libsource (lib "eagle-import") (part "CHIP-RESISTOR-0603"))
    )
    (comp (ref "R4")
      (value "3.24K")
      (footprint "eagle-import:R0603")
      (libsource (lib "eagle-import") (part "CHIP-RESISTOR-0603"))
    )
    (comp (ref "R5")
      (value "10K")
      (footprint "eagle-import:R0603")
      (libsource (lib "eagle-import") (part "CHIP-RESISTOR-0603"))
    )
    (comp (ref "R6")
      (value "5.9K")
      (footprint "eagle-import:R0603")
      (libsource (lib "eagle-import") (part "CHIP-RESISTOR-0603"))
    )
    (comp (ref "R7")
      (value "150")
      (footprint "eagle-import:R0805")
      (libsource (lib "eagle-import") (part "CHIP-RESISTOR-0805"))
    )
    (comp (ref "R8")
      (value "330")
      (footprint "eagle-import:R0603")
      (libsource (lib "eagle-import") (part "CHIP-RESISTOR-0603"))
    )
    (comp (ref "R9")
      (value "330")
      (footprint "eagle-import:R0603")
      (libsource (lib "eagle-import") (part "CHIP-RESISTOR-0603"))
    )
    (comp (ref "R34")
      (value "270")
      (footprint "eagle-import:R1206")
      (libsource (lib "eagle-import") (part "CHIP-RESISTOR-1206"))
    )
    (comp (ref "R35")
      (value "180")
      (footprint "eagle-import:R1206")
      (libsource (lib "eagle-import") (part "CHIP-RESISTOR-1206"))
    )
    (comp (ref "U1")
      (value "TPS5410DR")
      (footprint "eagle-import:SOIC8")
      (libsource (lib "eagle-import") (part "TPS5450_SOIC8"))
    )
    (comp (ref "U2")
      (value "TPS5410DR")
      (footprint "eagle-import:SOIC8")
      (libsource (lib "eagle-import") (part "TPS5450_SOIC8"))
    )
    (comp (ref "U3")
      (value "MAX3485EESA+T")
      (footprint "eagle-import:SOIC8")
      (libsource (lib "eagle-import") (part "MAX3485"))
    )
    (comp (ref "X1")
      (value "TE-282836-2")
      (footprint "eagle-import:W237-102")
      (libsource (lib "eagle-import") (part "TE-282836-2"))
    )
    (comp (ref "X2")
      (value "TE-282836-3")
      (footprint "eagle-import:W237-103")
      (libsource (lib "eagle-import") (part "TE-282836-3"))
    )
  )
  (nets
    (net (code "1") (name "3V3") (class "Default")
      (node (ref "C25") (pin "+") (pinfunction "+_+") (pintype "passive"))
      (node (ref "C6") (pin "2") (pinfunction "2_2") (pintype "passive"))
      (node (ref "C7") (pin "1") (pinfunction "1_1") (pintype "passive"))
      (node (ref "D6") (pin "+") (pinfunction "+_+") (pintype "passive"))
      (node (ref "L2") (pin "2") (pinfunction "2_2") (pintype "passive"))
      (node (ref "L5") (pin "2") (pinfunction "2_2") (pintype "passive"))
      (node (ref "L6") (pin "1") (pinfunction "1_1") (pintype "passive"))
      (node (ref "R10") (pin "1") (pinfunction "1_1") (pintype "passive"))
      (node (ref "R35") (pin "2") (pinfunction "2_2") (pintype "passive"))
      (node (ref "R5") (pin "2") (pinfunction "2_2") (pintype "passive"))
      (node (ref "R9") (pin "1") (pinfunction "1_1") (pintype "passive"))
      (node (ref "U3") (pin "8") (pinfunction "VCC_8") (pintype "power_in"))
      (node (ref "X11") (pin "3") (pinfunction "P$3_3") (pintype "bidirectional"))
      (node (ref "X15") (pin "3") (pinfunction "P$3_3") (pintype "bidirectional"))
      (node (ref "X19") (pin "3") (pinfunction "3_3") (pintype "bidirectional"))
      (node (ref "X19") (pin "4") (pinfunction "4_4") (pintype "bidirectional"))
      (node (ref "X20") (pin "3") (pinfunction "P$3_3") (pintype "bidirectional"))
      (node (ref "X24") (pin "3") (pinfunction "P$3_3") (pintype "bidirectional"))
      (node (ref "X26") (pin "3") (pinfunction "P$3_3") (pintype "bidirectional"))
      (node (ref "X30") (pin "3") (pinfunction "P$3_3") (pintype "bidirectional"))
      (node (ref "X32") (pin "3") (pinfunction "P$3_3") (pintype "bidirectional"))
      (node (ref "X36") (pin "3") (pinfunction "P$3_3") (pintype "bidirectional"))
      (node (ref "X38") (pin "3") (pinfunction "P$3_3") (pintype "bidirectional"))
      (node (ref "X40") (pin "4") (pinfunction "4_4") (pintype "bidirectional"))
      (node (ref "X42") (pin "3") (pinfunction "P$3_3") (pintype "bidirectional"))
      (node (ref "X44") (pin "3") (pinfunction "P$3_3") (pintype "bidirectional"))
      (node (ref "X46") (pin "4") (pinfunction "4_4") (pintype "bidirectional"))
      (node (ref "X47") (pin "4") (pinfunction "4_4") (pintype "bidirectional"))
      (node (ref "X48") (pin "3") (pinfunction "P$3_3") (pintype "bidirectional"))
      (node (ref "X50") (pin "3") (pinfunction "P$3_3") (pintype "bidirectional"))
      (node (ref "X53") (pin "3") (pinfunction "P$3_3") (pintype "bidirectional"))
    )
    (net (code "2") (name "3V3_STM") (class "Default")
      (node (ref "C13") (pin "1") (pinfunction "1_1") (pintype "passive"))
      (node (ref "C14") (pin "1") (pinfunction "1_1") (pintype "passive"))
      (node (ref "C15") (pin "1") (pinfunction "1_1") (pintype "passive"))
      (node (ref "C16") (pin "1") (pinfunction "1_1") (pintype "passive"))
      (node (ref "L3") (pin "2") (pinfunction "2_2") (pintype "passive"))
      (node (ref "L6") (pin "2") (pinfunction "2_2") (pintype "passive"))
      (node (ref "R33") (pin "1") (pinfunction "1_1") (pintype "passive"))
      (node (ref "U4") (pin "19") (pinfunction "VDD_19") (pintype "power_in"))
      (node (ref "U4") (pin "32") (pinfunction "VDD_32") (pintype "power_in"))
      (node (ref "U4") (pin "48") (pinfunction "VDD_48") (pintype "power_in"))
      (node (ref "U4") (pin "64") (pinfunction "VDD_64") (pintype "power_in"))
      (node (ref "X3") (pin "1") (pinfunction "VCC_1") (pintype "power_in"))
      (node (ref "X5") (pin "1") (pinfunction "1_1") (pintype "bidirectional"))
      (node (ref "X5") (pin "6") (pinfunction "6_6") (pintype "bidirectional"))
      (node (ref "X6") (pin "6") (pinfunction "6_6") (pintype "bidirectional"))
      (node (ref "X6") (pin "9") (pinfunction "9_9") (pintype "bidirectional"))
      (node (ref "X7") (pin "9") (pinfunction "9_9") (pintype "bidirectional"))
    )
    (net (code "3") (name "5V0") (class "Default")
      (node (ref "C24") (pin "+") (pinfunction "+_+") (pintype "passive"))
      (node (ref "C5") (pin "2") (pinfunction "2_2") (pintype "passive"))
      (node (ref "L1") (pin "2") (pinfunction "2_2") (pintype "passive"))
      (node (ref "R3") (pin "2") (pinfunction "2_2") (pintype "passive"))
      (node (ref "R34") (pin "2") (pinfunction "2_2") (pintype "passive"))
      (node (ref "X11") (pin "1") (pinfunction "P$1_1") (pintype "bidirectional"))
      (node (ref "X15") (pin "1") (pinfunction "P$1_1") (pintype "bidirectional"))
      (node (ref "X19") (pin "1") (pinfunction "1_1") (pintype "bidirectional"))
      (node (ref "X19") (pin "6") (pinfunction "6_6") (pintype "bidirectional"))
      (node (ref "X20") (pin "1") (pinfunction "P$1_1") (pintype "bidirectional"))
      (node (ref "X24") (pin "1") (pinfunction "P$1_1") (pintype "bidirectional"))
      (node (ref "X26") (pin "1") (pinfunction "P$1_1") (pintype "bidirectional"))
      (node (ref "X30") (pin "1") (pinfunction "P$1_1") (pintype "bidirectional"))
      (node (ref "X32") (pin "1") (pinfunction "P$1_1") (pintype "bidirectional"))
      (node (ref "X36") (pin "1") (pinfunction "P$1_1") (pintype "bidirectional"))
      (node (ref "X38") (pin "1") (pinfunction "P$1_1") (pintype "bidirectional"))
      (node (ref "X40") (pin "5") (pinfunction "5_5") (pintype "bidirectional"))
      (node (ref "X42") (pin "1") (pinfunction "P$1_1") (pintype "bidirectional"))
      (node (ref "X44") (pin "1") (pinfunction "P$1_1") (pintype "bidirectional"))
      (node (ref "X46") (pin "3") (pinfunction "3_3") (pintype "bidirectional"))
      (node (ref "X47") (pin "3") (pinfunction "3_3") (pintype "bidirectional"))
      (node (ref "X48") (pin "1") (pinfunction "P$1_1") (pintype "bidirectional"))
      (node (ref "X50") (pin "1") (pinfunction "P$1_1") (pintype "bidirectional"))
      (node (ref "X53") (pin "1") (pinfunction "P$1_1") (pintype "bidirectional"))
    )
    (net (code "4") (name "12V") (class "Default")
      (node (ref "C1") (pin "1") (pinfunction "1_1") (pintype "passive"))
      (node (ref "C2") (pin "1") (pinfunction "1_1") (pintype "passive"))
      (node (ref "R1") (pin "2") (pinfunction "2_2") (pintype "passive"))
      (node (ref "R2") (pin "2") (pinfunction "2_2") (pintype "passive"))
      (node (ref "U1") (pin "7") (pinfunction "VIN_7") (pintype "passive"))
      (node (ref "U2") (pin "7") (pinfunction "VIN_7") (pintype "passive"))
      (node (ref "X1") (pin "1") (pinfunction "1_1") (pintype "bidirectional"))
      (node (ref "X40") (pin "6") (pinfunction "6_6") (pintype "bidirectional"))
      (node (ref "X46") (pin "2") (pinfunction "2_2") (pintype "bidirectional"))
      (node (ref "X47") (pin "2") (pinfunction "2_2") (pintype "bidirectional"))
    )
    (net (code "5") (name "ADC1_10") (class "Default")
      (node (ref "U4") (pin "8") (pinfunction "PC0_8") (pintype "bidirectional"))
      (node (ref "X51") (pin "1") (pinfunction "1_1") (pintype "passive"))
      (node (ref "X6") (pin "13") (pinfunction "13_13") (pintype "bidirectional"))
    )
    (net (code "6") (name "ADC1_11") (class "Default")
      (node (ref "U4") (pin "9") (pinfunction "PC1_9") (pintype "bidirectional"))
      (node (ref "X51") (pin "2") (pinfunction "2_2") (pintype "passive"))
      (node (ref "X6") (pin "2") (pinfunction "2_2") (pintype "bidirectional"))
    )
    (net (code "7") (name "ADC1_12") (class "Default")
      (node (ref "U4") (pin "10") (pinfunction "PC2_10") (pintype "bidirectional"))
      (node (ref "X51") (pin "3") (pinfunction "3_3") (pintype "passive"))
      (node (ref "X6") (pin "12") (pinfunction "12_12") (pintype "bidirectional"))
    )
    (net (code "8") (name "ADC1_13") (class "Default")
      (node (ref "U4") (pin "11") (pinfunction "PC3_11") (pintype "bidirectional"))
      (node (ref "X51") (pin "4") (pinfunction "4_4") (pintype "passive"))
      (node (ref "X6") (pin "3") (pinfunction "3_3") (pintype "bidirectional"))
    )
    (net (code "9") (name "BOOT0") (class "Default")
      (node (ref "R13") (pin "1") (pinfunction "1_1") (pintype "passive"))
      (node (ref "U4") (pin "60") (pinfunction "BOOT0_60") (pintype "input"))
      (node (ref "X8") (pin "6") (pinfunction "6_6") (pintype "bidirectional"))
    )
    (net (code "10") (name "BOOT1") (class "Default")
      (node (ref "R14") (pin "1") (pinfunction "1_1") (pintype "passive"))
      (node (ref "U4") (pin "28") (pinfunction "PB2_28") (pintype "bidirectional"))
      (node (ref "X7") (pin "14") (pinfunction "14_14") (pintype "bidirectional"))
    )
    (net (code "11") (name "EXT") (class "Default")
      (node (ref "X41") (pin "1") (pinfunction "1_1") (pintype "bidirectional"))
      (node (ref "X46") (pin "1") (pinfunction "1_1") (pintype "bidirectional"))
      (node (ref "X47") (pin "1") (pinfunction "1_1") (pintype "bidirectional"))
    )
    (net (code "12") (name "GND") (class "Default")
      (node (ref "ANT1") (pin "P$2") (pinfunction "GND_P$2") (pintype "bidirectional"))
      (node (ref "C1") (pin "2") (pinfunction "2_2") (pintype "passive"))
      (node (ref "C12") (pin "2") (pinfunction "2_2") (pintype "passive"))
      (node (ref "C13") (pin "2") (pinfunction "2_2") (pintype "passive"))
      (node (ref "C14") (pin "2") (pinfunction "2_2") (pintype "passive"))
      (node (ref "C15") (pin "2") (pinfunction "2_2") (pintype "passive"))
      (node (ref "C16") (pin "2") (pinfunction "2_2") (pintype "passive"))
      (node (ref "C17") (pin "2") (pinfunction "2_2") (pintype "passive"))
      (node (ref "C18") (pin "1") (pinfunction "1_1") (pintype "passive"))
      (node (ref "C19") (pin "2") (pinfunction "2_2") (pintype "passive"))
      (node (ref "C2") (pin "2") (pinfunction "2_2") (pintype "passive"))
      (node (ref "C20") (pin "1") (pinfunction "1_1") (pintype "passive"))
      (node (ref "C21") (pin "-") (pinfunction "-_-") (pintype "passive"))
      (node (ref "C23") (pin "2") (pinfunction "2_2") (pintype "passive"))
      (node (ref "C24") (pin "-") (pinfunction "-_-") (pintype "passive"))
      (node (ref "C25") (pin "-") (pinfunction "-_-") (pintype "passive"))
      (node (ref "C5") (pin "1") (pinfunction "1_1") (pintype "passive"))
      (node (ref "C6") (pin "1") (pinfunction "1_1") (pintype "passive"))
      (node (ref "C7") (pin "2") (pinfunction "2_2") (pintype "passive"))
      (node (ref "D1") (pin "+") (pinfunction "+_+") (pintype "passive"))
      (node (ref "D2") (pin "+") (pinfunction "+_+") (pintype "passive"))
      (node (ref "D3") (pin "-") (pinfunction "-_-") (pintype "passive"))
      (node (ref "L7") (pin "2") (pinfunction "2_2") (pintype "passive"))
      (node (ref "Q1") (pin "2") (pinfunction "S_2") (pintype "passive"))
      (node (ref "Q10") (pin "2") (pinfunction "S_2") (pintype "passive"))
      (node (ref "Q2") (pin "2") (pinfunction "S_2") (pintype "passive"))
      (node (ref "Q3") (pin "2") (pinfunction "S_2") (pintype "passive"))
      (node (ref "Q4") (pin "2") (pinfunction "S_2") (pintype "passive"))
      (node (ref "Q5") (pin "2") (pinfunction "S_2") (pintype "passive"))
      (node (ref "Q6") (pin "2") (pinfunction "S_2") (pintype "passive"))
      (node (ref "Q7") (pin "2") (pinfunction "S_2") (pintype "passive"))
      (node (ref "Q8") (pin "2") (pinfunction "S_2") (pintype "passive"))
      (node (ref "Q9") (pin "2") (pinfunction "S_2") (pintype "passive"))
      (node (ref "R15") (pin "1") (pinfunction "1_1") (pintype "passive"))
      (node (ref "R16") (pin "1") (pinfunction "1_1") (pintype "passive"))
      (node (ref "R17") (pin "1") (pinfunction "1_1") (pintype "passive"))
      (node (ref "R18") (pin "1") (pinfunction "1_1") (pintype "passive"))
      (node (ref "R21") (pin "1") (pinfunction "1_1") (pintype "passive"))
      (node (ref "R22") (pin "1") (pinfunction "1_1") (pintype "passive"))
      (node (ref "R23") (pin "1") (pinfunction "1_1") (pintype "passive"))
      (node (ref "R24") (pin "1") (pinfunction "1_1") (pintype "passive"))
      (node (ref "R27") (pin "1") (pinfunction "1_1") (pintype "passive"))
      (node (ref "R28") (pin "1") (pinfunction "1_1") (pintype "passive"))
      (node (ref "R29") (pin "1") (pinfunction "1_1") (pintype "passive"))
      (node (ref "R30") (pin "1") (pinfunction "1_1") (pintype "passive"))
      (node (ref "R34") (pin "1") (pinfunction "1_1") (pintype "passive"))
      (node (ref "R35") (pin "1") (pinfunction "1_1") (pintype "passive"))
      (node (ref "R4") (pin "1") (pinfunction "1_1") (pintype "passive"))
      (node (ref "R6") (pin "1") (pinfunction "1_1") (pintype "passive"))
      (node (ref "R8") (pin "1") (pinfunction "1_1") (pintype "passive"))
      (node (ref "SW1") (pin "P$2") (pinfunction "2_P$2") (pintype "passive"))
      (node (ref "U1") (pin "6") (pinfunction "GND_6") (pintype "passive"))
      (node (ref "U2") (pin "6") (pinfunction "GND_6") (pintype "passive"))
      (node (ref "U3") (pin "5") (pinfunction "GND_5") (pintype "power_in"))
      (node (ref "U4") (pin "12") (pinfunction "VSSA_12") (pintype "power_in"))
      (node (ref "U4") (pin "18") (pinfunction "VSS_18") (pintype "power_in"))
      (node (ref "U4") (pin "31") (pinfunction "VSS_31") (pintype "power_in"))
      (node (ref "U4") (pin "47") (pinfunction "VSS_47") (pintype "power_in"))
      (node (ref "U4") (pin "63") (pinfunction "VSS_63") (pintype "power_in"))
      (node (ref "U5") (pin "P1") (pinfunction "GND1_P1") (pintype "bidirectional"))
      (node (ref "U5") (pin "P16") (pinfunction "GND3_P16") (pintype "bidirectional"))
      (node (ref "U5") (pin "P2") (pinfunction "GND2_P2") (pintype "bidirectional"))
      (node (ref "U5") (pin "P27") (pinfunction "GND4_P27") (pintype "bidirectional"))
      (node (ref "U5") (pin "P28") (pinfunction "GND5_P28") (pintype "bidirectional"))
      (node (ref "U5") (pin "P30") (pinfunction "GND6_P30") (pintype "bidirectional"))
      (node (ref "U5") (pin "P32") (pinfunction "GND7_P32") (pintype "bidirectional"))
      (node (ref "U5") (pin "P38") (pinfunction "GND8_P38") (pintype "bidirectional"))
      (node (ref "U5") (pin "P43") (pinfunction "GND9_P43") (pintype "bidirectional"))
      (node (ref "U5") (pin "P55") (pinfunction "GND1_P55") (pintype "bidirectional"))
      (node (ref "U5") (pin "P56") (pinfunction "GND1_P56") (pintype "bidirectional"))
      (node (ref "U5") (pin "P57") (pinfunction "GND1_P57") (pintype "bidirectional"))
      (node (ref "U5") (pin "P58") (pinfunction "GND1_P58") (pintype "bidirectional"))
      (node (ref "U5") (pin "P59") (pinfunction "GND1_P59") (pintype "bidirectional"))
      (node (ref "U5") (pin "P60") (pinfunction "GND1_P60") (pintype "bidirectional"))
      (node (ref "U5") (pin "P61") (pinfunction "GND1_P61") (pintype "bidirectional"))
      (node (ref "U5") (pin "P62") (pinfunction "GND1_P62") (pintype "bidirectional"))
      (node (ref "U5") (pin "P63") (pinfunction "GND1_P63") (pintype "bidirectional"))
      (node (ref "X1") (pin "2") (pinfunction "2_2") (pintype "bidirectional"))
      (node (ref "X10") (pin "5") (pinfunction "5_5") (pintype "bidirectional"))
      (node (ref "X12") (pin "4") (pinfunction "P$4_4") (pintype "bidirectional"))
      (node (ref "X16") (pin "6") (pinfunction "6_6") (pintype "passive"))
      (node (ref "X2") (pin "3") (pinfunction "3_3") (pintype "bidirectional"))
      (node (ref "X21") (pin "4") (pinfunction "P$4_4") (pintype "bidirectional"))
      (node (ref "X25") (pin "6") (pinfunction "6_6") (pintype "passive"))
      (node (ref "X27") (pin "4") (pinfunction "P$4_4") (pintype "bidirectional"))
      (node (ref "X3") (pin "3") (pinfunction "GND_3") (pintype "power_in"))
      (node (ref "X3") (pin "5") (pinfunction "GND_5") (pintype "power_in"))
      (node (ref "X3") (pin "7") (pinfunction "KEY_7") (pintype "bidirectional"))
      (node (ref "X3") (pin "9") (pinfunction "GNDDETECT_9") (pintype "bidirectional"))
      (node (ref "X31") (pin "6") (pinfunction "6_6") (pintype "passive"))
      (node (ref "X33") (pin "4") (pinfunction "P$4_4") (pintype "bidirectional"))
      (node (ref "X37") (pin "4") (pinfunction "P$4_4") (pintype "bidirectional"))
      (node (ref "X39") (pin "6") (pinfunction "6_6") (pintype "passive"))
      (node (ref "X4") (pin "2") (pinfunction "2_2") (pintype "bidirectional"))
      (node (ref "X40") (pin "1") (pinfunction "1_1") (pintype "bidirectional"))
      (node (ref "X40") (pin "2") (pinfunction "2_2") (pintype "bidirectional"))
      (node (ref "X40") (pin "3") (pinfunction "3_3") (pintype "bidirectional"))
      (node (ref "X41") (pin "2") (pinfunction "2_2") (pintype "bidirectional"))
      (node (ref "X43") (pin "4") (pinfunction "P$4_4") (pintype "bidirectional"))
      (node (ref "X45") (pin "6") (pinfunction "6_6") (pintype "passive"))
      (node (ref "X49") (pin "4") (pinfunction "P$4_4") (pintype "bidirectional"))
      (node (ref "X5") (pin "3") (pinfunction "3_3") (pintype "bidirectional"))
      (node (ref "X5") (pin "4") (pinfunction "4_4") (pintype "bidirectional"))
      (node (ref "X51") (pin "6") (pinfunction "6_6") (pintype "passive"))
      (node (ref "X54") (pin "4") (pinfunction "P$4_4") (pintype "bidirectional"))
      (node (ref "X55") (pin "GND1") (pinfunction "GND_GND1") (pintype "bidirectional"))
      (node (ref "X55") (pin "GND2") (pinfunction "GND1_GND2") (pintype "bidirectional"))
      (node (ref "X56") (pin "-") (pinfunction "-_-") (pintype "passive"))
      (node (ref "X6") (pin "7") (pinfunction "7_7") (pintype "bidirectional"))
      (node (ref "X6") (pin "8") (pinfunction "8_8") (pintype "bidirectional"))
      (node (ref "X7") (pin "7") (pinfunction "7_7") (pintype "bidirectional"))
      (node (ref "X7") (pin "8") (pinfunction "8_8") (pintype "bidirectional"))
    )
    (net (code "13") (name "GNDA") (class "Default")
      (node (ref "C10") (pin "1") (pinfunction "1_1") (pintype "passive"))
      (node (ref "C11") (pin "1") (pinfunction "1_1") (pintype "passive"))
      (node (ref "C8") (pin "1") (pinfunction "1_1") (pintype "passive"))
      (node (ref "C9") (pin "1") (pinfunction "1_1") (pintype "passive"))
      (node (ref "Y2") (pin "2") (pinfunction "GND_2") (pintype "passive"))
      (node (ref "Y2") (pin "4") (pinfunction "GND_4") (pintype "passive"))
    )
    (net (code "14") (name "GROUP_1") (class "Default")
      (node (ref "X13") (pin "1") (pinfunction "1_1") (pintype "bidirectional"))
      (node (ref "X17") (pin "1") (pinfunction "1_1") (pintype "bidirectional"))
      (node (ref "X22") (pin "1") (pinfunction "1_1") (pintype "bidirectional"))
      (node (ref "X28") (pin "1") (pinfunction "1_1") (pintype "bidirectional"))
      (node (ref "X34") (pin "1") (pinfunction "1_1") (pintype "bidirectional"))
      (node (ref "X46") (pin "5") (pinfunction "5_5") (pintype "bidirectional"))
      (node (ref "X46") (pin "6") (pinfunction "6_6") (pintype "bidirectional"))
      (node (ref "X46") (pin "7") (pinfunction "7_7") (pintype "bidirectional"))
      (node (ref "X46") (pin "8") (pinfunction "8_8") (pintype "bidirectional"))
    )
    (net (code "15") (name "GROUP_2") (class "Default")
      (node (ref "X14") (pin "1") (pinfunction "1_1") (pintype "bidirectional"))
      (node (ref "X18") (pin "1") (pinfunction "1_1") (pintype "bidirectional"))
      (node (ref "X23") (pin "1") (pinfunction "1_1") (pintype "bidirectional"))
      (node (ref "X29") (pin "1") (pinfunction "1_1") (pintype "bidirectional"))
      (node (ref "X35") (pin "1") (pinfunction "1_1") (pintype "bidirectional"))
      (node (ref "X47") (pin "5") (pinfunction "5_5") (pintype "bidirectional"))
      (node (ref "X47") (pin "6") (pinfunction "6_6") (pintype "bidirectional"))
      (node (ref "X47") (pin "7") (pinfunction "7_7") (pintype "bidirectional"))
      (node (ref "X47") (pin "8") (pinfunction "8_8") (pintype "bidirectional"))
    )
    (net (code "16") (name "I2C2_SCL") (class "Default")
      (node (ref "R20") (pin "1") (pinfunction "1_1") (pintype "passive"))
      (node (ref "U4") (pin "29") (pinfunction "PB10_29") (pintype "bidirectional"))
      (node (ref "X12") (pin "2") (pinfunction "P$2_2") (pintype "bidirectional"))
      (node (ref "X21") (pin "2") (pinfunction "P$2_2") (pintype "bidirectional"))
      (node (ref "X27") (pin "2") (pinfunction "P$2_2") (pintype "bidirectional"))
      (node (ref "X33") (pin "2") (pinfunction "P$2_2") (pintype "bidirectional"))
      (node (ref "X37") (pin "2") (pinfunction "P$2_2") (pintype "bidirectional"))
      (node (ref "X7") (pin "1") (pinfunction "1_1") (pintype "bidirectional"))
    )
    (net (code "17") (name "I2C2_SDA") (class "Default")
      (node (ref "R19") (pin "1") (pinfunction "1_1") (pintype "passive"))
      (node (ref "U4") (pin "62") (pinfunction "PB9_62") (pintype "bidirectional"))
      (node (ref "X12") (pin "1") (pinfunction "P$1_1") (pintype "bidirectional"))
      (node (ref "X21") (pin "1") (pinfunction "P$1_1") (pintype "bidirectional"))
      (node (ref "X27") (pin "1") (pinfunction "P$1_1") (pintype "bidirectional"))
      (node (ref "X33") (pin "1") (pinfunction "P$1_1") (pintype "bidirectional"))
      (node (ref "X37") (pin "1") (pinfunction "P$1_1") (pintype "bidirectional"))
      (node (ref "X8") (pin "7") (pinfunction "7_7") (pintype "bidirectional"))
    )
    (net (code "18") (name "I2C3_SCL") (class "Default")
      (node (ref "R26") (pin "1") (pinfunction "1_1") (pintype "passive"))
      (node (ref "U4") (pin "41") (pinfunction "PA8_41") (pintype "bidirectional"))
      (node (ref "X43") (pin "2") (pinfunction "P$2_2") (pintype "bidirectional"))
      (node (ref "X49") (pin "2") (pinfunction "P$2_2") (pintype "bidirectional"))
      (node (ref "X54") (pin "2") (pinfunction "P$2_2") (pintype "bidirectional"))
      (node (ref "X9") (pin "12") (pinfunction "12_12") (pintype "bidirectional"))
    )
    (net (code "19") (name "I2C3_SDA") (class "Default")
      (node (ref "R25") (pin "1") (pinfunction "1_1") (pintype "passive"))
      (node (ref "U4") (pin "61") (pinfunction "PB8_61") (pintype "bidirectional"))
      (node (ref "X43") (pin "1") (pinfunction "P$1_1") (pintype "bidirectional"))
      (node (ref "X49") (pin "1") (pinfunction "P$1_1") (pintype "bidirectional"))
      (node (ref "X54") (pin "1") (pinfunction "P$1_1") (pintype "bidirectional"))
      (node (ref "X8") (pin "8") (pinfunction "8_8") (pintype "bidirectional"))
    )
    (net (code "20") (name "Net-(ANT1-ANT)") (class "Default")
      (node (ref "ANT1") (pin "P$1") (pinfunction "ANT_P$1") (pintype "bidirectional"))
      (node (ref "C20") (pin "2") (pinfunction "2_2") (pintype "passive"))
      (node (ref "L4") (pin "2") (pinfunction "2_2") (pintype "passive"))
    )
    (net (code "21") (name "Net-(C18-Pad2)") (class "Default")
      (node (ref "C18") (pin "2") (pinfunction "2_2") (pintype "passive"))
      (node (ref "L4") (pin "1") (pinfunction "1_1") (pintype "passive"))
      (node (ref "R31") (pin "2") (pinfunction "2_2") (pintype "passive"))
    )
    (net (code "22") (name "Net-(C22-Pad2)") (class "Default")
      (node (ref "C22") (pin "2") (pinfunction "2_2") (pintype "passive"))
      (node (ref "R32") (pin "2") (pinfunction "2_2") (pintype "passive"))
    )
    (net (code "23") (name "Net-(D3-Pad+)") (class "Default")
      (node (ref "D3") (pin "+") (pinfunction "+_+") (pintype "passive"))
      (node (ref "R10") (pin "2") (pinfunction "2_2") (pintype "passive"))
    )
    (net (code "24") (name "Net-(D4-Pad+)") (class "Default")
      (node (ref "D4") (pin "+") (pinfunction "+_+") (pintype "passive"))
      (node (ref "R11") (pin "2") (pinfunction "2_2") (pintype "passive"))
    )
    (net (code "25") (name "Net-(D4-Pad-)") (class "Default")
      (node (ref "D4") (pin "-") (pinfunction "-_-") (pintype "passive"))
      (node (ref "D5") (pin "-") (pinfunction "-_-") (pintype "passive"))
      (node (ref "X4") (pin "1") (pinfunction "1_1") (pintype "bidirectional"))
    )
    (net (code "26") (name "Net-(D5-Pad+)") (class "Default")
      (node (ref "D5") (pin "+") (pinfunction "+_+") (pintype "passive"))
      (node (ref "R12") (pin "2") (pinfunction "2_2") (pintype "passive"))
    )
    (net (code "27") (name "Net-(D7-Pad+)") (class "Default")
      (node (ref "D7") (pin "+") (pinfunction "+_+") (pintype "passive"))
      (node (ref "X56") (pin "+") (pinfunction "+_+") (pintype "passive"))
    )
    (net (code "28") (name "Net-(Q1-D)") (class "Default")
      (node (ref "Q1") (pin "3") (pinfunction "D_3") (pintype "passive"))
      (node (ref "X13") (pin "2") (pinfunction "2_2") (pintype "bidirectional"))
    )
    (net (code "29") (name "Net-(Q2-D)") (class "Default")
      (node (ref "Q2") (pin "3") (pinfunction "D_3") (pintype "passive"))
      (node (ref "X14") (pin "2") (pinfunction "2_2") (pintype "bidirectional"))
    )
    (net (code "30") (name "Net-(Q3-D)") (class "Default")
      (node (ref "Q3") (pin "3") (pinfunction "D_3") (pintype "passive"))
      (node (ref "X17") (pin "2") (pinfunction "2_2") (pintype "bidirectional"))
    )
    (net (code "31") (name "Net-(Q4-D)") (class "Default")
      (node (ref "Q4") (pin "3") (pinfunction "D_3") (pintype "passive"))
      (node (ref "X18") (pin "2") (pinfunction "2_2") (pintype "bidirectional"))
    )
    (net (code "32") (name "Net-(Q5-D)") (class "Default")
      (node (ref "Q5") (pin "3") (pinfunction "D_3") (pintype "passive"))
      (node (ref "X22") (pin "2") (pinfunction "2_2") (pintype "bidirectional"))
    )
    (net (code "33") (name "Net-(Q6-D)") (class "Default")
      (node (ref "Q6") (pin "3") (pinfunction "D_3") (pintype "passive"))
      (node (ref "X23") (pin "2") (pinfunction "2_2") (pintype "bidirectional"))
    )
    (net (code "34") (name "Net-(Q7-D)") (class "Default")
      (node (ref "Q7") (pin "3") (pinfunction "D_3") (pintype "passive"))
      (node (ref "X28") (pin "2") (pinfunction "2_2") (pintype "bidirectional"))
    )
    (net (code "35") (name "Net-(Q8-D)") (class "Default")
      (node (ref "Q8") (pin "3") (pinfunction "D_3") (pintype "passive"))
      (node (ref "X29") (pin "2") (pinfunction "2_2") (pintype "bidirectional"))
    )
    (net (code "36") (name "Net-(Q9-D)") (class "Default")
      (node (ref "Q9") (pin "3") (pinfunction "D_3") (pintype "passive"))
      (node (ref "X34") (pin "2") (pinfunction "2_2") (pintype "bidirectional"))
    )
    (net (code "37") (name "Net-(Q10-D)") (class "Default")
      (node (ref "Q10") (pin "3") (pinfunction "D_3") (pintype "passive"))
      (node (ref "X35") (pin "2") (pinfunction "2_2") (pintype "bidirectional"))
    )
    (net (code "38") (name "Net-(R13-Pad2)") (class "Default")
      (node (ref "R13") (pin "2") (pinfunction "2_2") (pintype "passive"))
      (node (ref "X5") (pin "2") (pinfunction "2_2") (pintype "bidirectional"))
    )
    (net (code "39") (name "Net-(R14-Pad2)") (class "Default")
      (node (ref "R14") (pin "2") (pinfunction "2_2") (pintype "passive"))
      (node (ref "X5") (pin "5") (pinfunction "5_5") (pintype "bidirectional"))
    )
    (net (code "40") (name "Net-(R19-Pad2)") (class "Default")
      (node (ref "R19") (pin "2") (pinfunction "2_2") (pintype "passive"))
      (node (ref "R20") (pin "2") (pinfunction "2_2") (pintype "passive"))
      (node (ref "X19") (pin "2") (pinfunction "2_2") (pintype "bidirectional"))
    )
    (net (code "41") (name "Net-(R25-Pad2)") (class "Default")
      (node (ref "R25") (pin "2") (pinfunction "2_2") (pintype "passive"))
      (node (ref "R26") (pin "2") (pinfunction "2_2") (pintype "passive"))
      (node (ref "X19") (pin "5") (pinfunction "5_5") (pintype "bidirectional"))
    )
    (net (code "42") (name "Net-(U1-BOOT)") (class "Default")
      (node (ref "C3") (pin "1") (pinfunction "1_1") (pintype "passive"))
      (node (ref "U1") (pin "1") (pinfunction "BOOT_1") (pintype "passive"))
    )
    (net (code "43") (name "Net-(U1-ENA)") (class "Default")
      (node (ref "R1") (pin "1") (pinfunction "1_1") (pintype "passive"))
      (node (ref "U1") (pin "5") (pinfunction "ENA_5") (pintype "passive"))
    )
    (net (code "44") (name "Net-(U1-PH)") (class "Default")
      (node (ref "C3") (pin "2") (pinfunction "2_2") (pintype "passive"))
      (node (ref "D1") (pin "-") (pinfunction "-_-") (pintype "passive"))
      (node (ref "L1") (pin "1") (pinfunction "1_1") (pintype "passive"))
      (node (ref "U1") (pin "8") (pinfunction "PH_8") (pintype "passive"))
    )
    (net (code "45") (name "Net-(U1-VSEN)") (class "Default")
      (node (ref "R3") (pin "1") (pinfunction "1_1") (pintype "passive"))
      (node (ref "R4") (pin "2") (pinfunction "2_2") (pintype "passive"))
      (node (ref "U1") (pin "4") (pinfunction "VSEN_4") (pintype "passive"))
    )
    (net (code "46") (name "Net-(U2-BOOT)") (class "Default")
      (node (ref "C4") (pin "1") (pinfunction "1_1") (pintype "passive"))
      (node (ref "U2") (pin "1") (pinfunction "BOOT_1") (pintype "passive"))
    )
    (net (code "47") (name "Net-(U2-ENA)") (class "Default")
      (node (ref "R2") (pin "1") (pinfunction "1_1") (pintype "passive"))
      (node (ref "U2") (pin "5") (pinfunction "ENA_5") (pintype "passive"))
    )
    (net (code "48") (name "Net-(U2-PH)") (class "Default")
      (node (ref "C4") (pin "2") (pinfunction "2_2") (pintype "passive"))
      (node (ref "D2") (pin "-") (pinfunction "-_-") (pintype "passive"))
      (node (ref "L2") (pin "1") (pinfunction "1_1") (pintype "passive"))
      (node (ref "U2") (pin "8") (pinfunction "PH_8") (pintype "passive"))
    )
    (net (code "49") (name "Net-(U2-VSEN)") (class "Default")
      (node (ref "R5") (pin "1") (pinfunction "1_1") (pintype "passive"))
      (node (ref "R6") (pin "2") (pinfunction "2_2") (pintype "passive"))
      (node (ref "U2") (pin "4") (pinfunction "VSEN_4") (pintype "passive"))
    )
    (net (code "50") (name "Net-(U3-A)") (class "Default")
      (node (ref "R7") (pin "2") (pinfunction "2_2") (pintype "passive"))
      (node (ref "R9") (pin "2") (pinfunction "2_2") (pintype "passive"))
      (node (ref "U3") (pin "6") (pinfunction "A_6") (pintype "bidirectional"))
      (node (ref "X2") (pin "1") (pinfunction "1_1") (pintype "bidirectional"))
    )
    (net (code "51") (name "Net-(U3-B)") (class "Default")
      (node (ref "R7") (pin "1") (pinfunction "1_1") (pintype "passive"))
      (node (ref "R8") (pin "2") (pinfunction "2_2") (pintype "passive"))
      (node (ref "U3") (pin "7") (pinfunction "B_7") (pintype "bidirectional"))
      (node (ref "X2") (pin "2") (pinfunction "2_2") (pintype "bidirectional"))
    )
    (net (code "52") (name "Net-(U4A-OSC_IN)") (class "Default")
      (node (ref "C9") (pin "2") (pinfunction "2_2") (pintype "passive"))
      (node (ref "U4") (pin "5") (pinfunction "OSC_IN_5") (pintype "bidirectional"))
      (node (ref "Y2") (pin "1") (pinfunction "1_1") (pintype "passive"))
    )
    (net (code "53") (name "Net-(U4A-OSC_OUT)") (class "Default")
      (node (ref "C11") (pin "2") (pinfunction "2_2") (pintype "passive"))
      (node (ref "U4") (pin "6") (pinfunction "OSC_OUT_6") (pintype "bidirectional"))
      (node (ref "Y2") (pin "3") (pinfunction "2_3") (pintype "passive"))
    )
    (net (code "54") (name "Net-(U4A-PC14)") (class "Default")
      (node (ref "C8") (pin "2") (pinfunction "2_2") (pintype "passive"))
      (node (ref "U4") (pin "3") (pinfunction "PC14_3") (pintype "bidirectional"))
      (node (ref "Y1") (pin "1") (pinfunction "1_1") (pintype "passive"))
    )
    (net (code "55") (name "Net-(U4A-PC15)") (class "Default")
      (node (ref "C10") (pin "2") (pinfunction "2_2") (pintype "passive"))
      (node (ref "U4") (pin "4") (pinfunction "PC15_4") (pintype "bidirectional"))
      (node (ref "Y1") (pin "2") (pinfunction "2_2") (pintype "passive"))
    )
    (net (code "56") (name "Net-(U4A-VCAP1)") (class "Default")
      (node (ref "C12") (pin "1") (pinfunction "1_1") (pintype "passive"))
      (node (ref "U4") (pin "30") (pinfunction "VCAP1_30") (pintype "power_in"))
    )
    (net (code "57") (name "Net-(U5-RES2)") (class "Default")
      (node (ref "R15") (pin "2") (pinfunction "2_2") (pintype "passive"))
      (node (ref "U5") (pin "P21") (pinfunction "RES2_P21") (pintype "bidirectional"))
    )
    (net (code "58") (name "Net-(U5-RF_BG)") (class "Default")
      (node (ref "R31") (pin "1") (pinfunction "1_1") (pintype "passive"))
      (node (ref "R32") (pin "1") (pinfunction "1_1") (pintype "passive"))
      (node (ref "U5") (pin "P31") (pinfunction "RF_BG_P31") (pintype "bidirectional"))
    )
    (net (code "59") (name "Net-(U5-SOP2)") (class "Default")
      (node (ref "R16") (pin "2") (pinfunction "2_2") (pintype "passive"))
      (node (ref "U5") (pin "P23") (pinfunction "SOP2_P23") (pintype "bidirectional"))
    )
    (net (code "60") (name "Net-(U5-TEST_58)") (class "Default")
      (node (ref "U5") (pin "P48") (pinfunction "TEST_58_P48") (pintype "bidirectional"))
      (node (ref "X10") (pin "1") (pinfunction "1_1") (pintype "bidirectional"))
    )
    (net (code "61") (name "Net-(U5-TEST_59)") (class "Default")
      (node (ref "U5") (pin "P49") (pinfunction "TEST_59_P49") (pintype "bidirectional"))
      (node (ref "X10") (pin "2") (pinfunction "2_2") (pintype "bidirectional"))
    )
    (net (code "62") (name "Net-(U5-TEST_60)") (class "Default")
      (node (ref "U5") (pin "P50") (pinfunction "TEST_60_P50") (pintype "bidirectional"))
      (node (ref "X10") (pin "3") (pinfunction "3_3") (pintype "bidirectional"))
    )
    (net (code "63") (name "Net-(U5-TEST_62)") (class "Default")
      (node (ref "U5") (pin "P52") (pinfunction "TEST_62_P52") (pintype "bidirectional"))
      (node (ref "X10") (pin "4") (pinfunction "4_4") (pintype "bidirectional"))
    )
    (net (code "64") (name "Net-(U5-VBAT_ANA)") (class "Default")
      (node (ref "C19") (pin "1") (pinfunction "1_1") (pintype "passive"))
      (node (ref "C21") (pin "+") (pinfunction "+_+") (pintype "passive"))
      (node (ref "L5") (pin "1") (pinfunction "1_1") (pintype "passive"))
      (node (ref "U5") (pin "P36") (pinfunction "VBAT_ANA_P36") (pintype "bidirectional"))
      (node (ref "U5") (pin "P37") (pinfunction "VBAT_PA_P37") (pintype "bidirectional"))
      (node (ref "U5") (pin "P40") (pinfunction "VBAT_DIG_IO_P40") (pintype "bidirectional"))
    )
    (net (code "65") (name "Net-(X11-P$2)") (class "Default")
      (node (ref "X11") (pin "2") (pinfunction "P$2_2") (pintype "bidirectional"))
      (node (ref "X12") (pin "3") (pinfunction "P$3_3") (pintype "bidirectional"))
    )
    (net (code "66") (name "Net-(X15-P$2)") (class "Default")
      (node (ref "X15") (pin "2") (pinfunction "P$2_2") (pintype "bidirectional"))
      (node (ref "X16") (pin "5") (pinfunction "5_5") (pintype "passive"))
    )
    (net (code "67") (name "Net-(X20-P$2)") (class "Default")
      (node (ref "X20") (pin "2") (pinfunction "P$2_2") (pintype "bidirectional"))
      (node (ref "X21") (pin "3") (pinfunction "P$3_3") (pintype "bidirectional"))
    )
    (net (code "68") (name "Net-(X24-P$2)") (class "Default")
      (node (ref "X24") (pin "2") (pinfunction "P$2_2") (pintype "bidirectional"))
      (node (ref "X25") (pin "5") (pinfunction "5_5") (pintype "passive"))
    )
    (net (code "69") (name "Net-(X26-P$2)") (class "Default")
      (node (ref "X26") (pin "2") (pinfunction "P$2_2") (pintype "bidirectional"))
      (node (ref "X27") (pin "3") (pinfunction "P$3_3") (pintype "bidirectional"))
    )
    (net (code "70") (name "Net-(X30-P$2)") (class "Default")
      (node (ref "X30") (pin "2") (pinfunction "P$2_2") (pintype "bidirectional"))
      (node (ref "X31") (pin "5") (pinfunction "5_5") (pintype "passive"))
    )
    (net (code "71") (name "Net-(X32-P$2)") (class "Default")
      (node (ref "X32") (pin "2") (pinfunction "P$2_2") (pintype "bidirectional"))
      (node (ref "X33") (pin "3") (pinfunction "P$3_3") (pintype "bidirectional"))
    )
    (net (code "72") (name "Net-(X36-P$2)") (class "Default")
      (node (ref "X36") (pin "2") (pinfunction "P$2_2") (pintype "bidirectional"))
      (node (ref "X37") (pin "3") (pinfunction "P$3_3") (pintype "bidirectional"))
    )
    (net (code "73") (name "Net-(X38-P$2)") (class "Default")
      (node (ref "X38") (pin "2") (pinfunction "P$2_2") (pintype "bidirectional"))
      (node (ref "X39") (pin "5") (pinfunction "5_5") (pintype "passive"))
    )
    (net (code "74") (name "Net-(X42-P$2)") (class "Default")
      (node (ref "X42") (pin "2") (pinfunction "P$2_2") (pintype "bidirectional"))
      (node (ref "X43") (pin "3") (pinfunction "P$3_3") (pintype "bidirectional"))
    )
    (net (code "75") (name "Net-(X44-P$2)") (class "Default")
      (node (ref "X44") (pin "2") (pinfunction "P$2_2") (pintype "bidirectional"))
      (node (ref "X45") (pin "5") (pinfunction "5_5") (pintype "passive"))
    )
    (net (code "76") (name "Net-(X48-P$2)") (class "Default")
      (node (ref "X48") (pin "2") (pinfunction "P$2_2") (pintype "bidirectional"))
      (node (ref "X49") (pin "3") (pinfunction "P$3_3") (pintype "bidirectional"))
    )
    (net (code "77") (name "Net-(X50-P$2)") (class "Default")
      (node (ref "X50") (pin "2") (pinfunction "P$2_2") (pintype "bidirectional"))
      (node (ref "X51") (pin "5") (pinfunction "5_5") (pintype "passive"))
    )
    (net (code "78") (name "Net-(X53-P$2)") (class "Default")
      (node (ref "X53") (pin "2") (pinfunction "P$2_2") (pintype "bidirectional"))
      (node (ref "X54") (pin "3") (pinfunction "P$3_3") (pintype "bidirectional"))
    )
    (net (code "79") (name "Net-(X55-ANT)") (class "Default")
      (node (ref "C22") (pin "1") (pinfunction "1_1") (pintype "passive"))
      (node (ref "L7") (pin "1") (pinfunction "1_1") (pintype "passive"))
      (node (ref "X55") (pin "D") (pinfunction "ANT_D") (pintype "bidirectional"))
    )
    (net (code "80") (name "PA_4") (class "Default")
      (node (ref "U4") (pin "20") (pinfunction "PA4_20") (pintype "bidirectional"))
      (node (ref "U5") (pin "P11") (pinfunction "INTR_P11") (pintype "bidirectional"))
      (node (ref "X7") (pin "10") (pinfunction "10_10") (pintype "bidirectional"))
    )
    (net (code "81") (name "PA_15") (class "Default")
      (node (ref "U4") (pin "50") (pinfunction "PA15_50") (pintype "bidirectional"))
      (node (ref "U5") (pin "P4") (pinfunction "~{HIB}_P4") (pintype "bidirectional"))
      (node (ref "X8") (pin "1") (pinfunction "1_1") (pintype "bidirectional"))
    )
    (net (code "82") (name "PB_0") (class "Default")
      (node (ref "Q1") (pin "1") (pinfunction "G_1") (pintype "passive"))
      (node (ref "R17") (pin "2") (pinfunction "2_2") (pintype "passive"))
      (node (ref "U4") (pin "26") (pinfunction "PB0_26") (pintype "bidirectional"))
      (node (ref "X52") (pin "1") (pinfunction "1_1") (pintype "passive"))
      (node (ref "X7") (pin "13") (pinfunction "13_13") (pintype "bidirectional"))
    )
    (net (code "83") (name "PB_1") (class "Default")
      (node (ref "Q3") (pin "1") (pinfunction "G_1") (pintype "passive"))
      (node (ref "R21") (pin "2") (pinfunction "2_2") (pintype "passive"))
      (node (ref "U4") (pin "27") (pinfunction "PB1_27") (pintype "bidirectional"))
      (node (ref "X52") (pin "2") (pinfunction "2_2") (pintype "passive"))
      (node (ref "X7") (pin "2") (pinfunction "2_2") (pintype "bidirectional"))
    )
    (net (code "84") (name "PB_4") (class "Default")
      (node (ref "Q5") (pin "1") (pinfunction "G_1") (pintype "passive"))
      (node (ref "R23") (pin "2") (pinfunction "2_2") (pintype "passive"))
      (node (ref "U4") (pin "56") (pinfunction "PB4_56") (pintype "bidirectional"))
      (node (ref "X52") (pin "3") (pinfunction "3_3") (pintype "passive"))
      (node (ref "X8") (pin "4") (pinfunction "4_4") (pintype "bidirectional"))
    )
    (net (code "85") (name "PB_5") (class "Default")
      (node (ref "Q7") (pin "1") (pinfunction "G_1") (pintype "passive"))
      (node (ref "R27") (pin "2") (pinfunction "2_2") (pintype "passive"))
      (node (ref "U4") (pin "57") (pinfunction "PB5_57") (pintype "bidirectional"))
      (node (ref "X52") (pin "4") (pinfunction "4_4") (pintype "passive"))
      (node (ref "X8") (pin "10") (pinfunction "10_10") (pintype "bidirectional"))
    )
    (net (code "86") (name "PB_6") (class "Default")
      (node (ref "Q9") (pin "1") (pinfunction "G_1") (pintype "passive"))
      (node (ref "R29") (pin "2") (pinfunction "2_2") (pintype "passive"))
      (node (ref "U4") (pin "58") (pinfunction "PB6_58") (pintype "bidirectional"))
      (node (ref "X52") (pin "5") (pinfunction "5_5") (pintype "passive"))
      (node (ref "X8") (pin "5") (pinfunction "5_5") (pintype "bidirectional"))
    )
    (net (code "87") (name "PB_7") (class "Default")
      (node (ref "Q2") (pin "1") (pinfunction "G_1") (pintype "passive"))
      (node (ref "R18") (pin "2") (pinfunction "2_2") (pintype "passive"))
      (node (ref "U4") (pin "59") (pinfunction "PB7_59") (pintype "bidirectional"))
      (node (ref "X52") (pin "6") (pinfunction "6_6") (pintype "passive"))
      (node (ref "X8") (pin "9") (pinfunction "9_9") (pintype "bidirectional"))
    )
    (net (code "88") (name "PB_12") (class "Default")
      (node (ref "Q4") (pin "1") (pinfunction "G_1") (pintype "passive"))
      (node (ref "R22") (pin "2") (pinfunction "2_2") (pintype "passive"))
      (node (ref "U4") (pin "33") (pinfunction "PB12_33") (pintype "bidirectional"))
      (node (ref "X52") (pin "7") (pinfunction "7_7") (pintype "passive"))
      (node (ref "X9") (pin "8") (pinfunction "8_8") (pintype "bidirectional"))
    )
    (net (code "89") (name "PC_4") (class "Default")
      (node (ref "U4") (pin "24") (pinfunction "PC4_24") (pintype "bidirectional"))
      (node (ref "U5") (pin "P8") (pinfunction "~{CS}_P8") (pintype "bidirectional"))
      (node (ref "X7") (pin "12") (pinfunction "12_12") (pintype "bidirectional"))
    )
    (net (code "90") (name "PC_6") (class "Default")
      (node (ref "U4") (pin "37") (pinfunction "PC6_37") (pintype "bidirectional"))
      (node (ref "X25") (pin "4") (pinfunction "4_4") (pintype "passive"))
      (node (ref "X9") (pin "10") (pinfunction "10_10") (pintype "bidirectional"))
    )
    (net (code "91") (name "PC_7") (class "Default")
      (node (ref "U4") (pin "38") (pinfunction "PC7_38") (pintype "bidirectional"))
      (node (ref "X31") (pin "4") (pinfunction "4_4") (pintype "passive"))
      (node (ref "X9") (pin "5") (pinfunction "5_5") (pintype "bidirectional"))
    )
    (net (code "92") (name "PC_8") (class "Default")
      (node (ref "U4") (pin "39") (pinfunction "PC8_39") (pintype "bidirectional"))
      (node (ref "X39") (pin "4") (pinfunction "4_4") (pintype "passive"))
      (node (ref "X9") (pin "11") (pinfunction "11_11") (pintype "bidirectional"))
    )
    (net (code "93") (name "PC_9") (class "Default")
      (node (ref "U4") (pin "40") (pinfunction "PC9_40") (pintype "bidirectional"))
      (node (ref "X45") (pin "4") (pinfunction "4_4") (pintype "passive"))
      (node (ref "X9") (pin "4") (pinfunction "4_4") (pintype "bidirectional"))
    )
    (net (code "94") (name "PC_11") (class "Default")
      (node (ref "Q6") (pin "1") (pinfunction "G_1") (pintype "passive"))
      (node (ref "R24") (pin "2") (pinfunction "2_2") (pintype "passive"))
      (node (ref "U4") (pin "52") (pinfunction "PC11_52") (pintype "bidirectional"))
      (node (ref "X52") (pin "8") (pinfunction "8_8") (pintype "passive"))
      (node (ref "X8") (pin "2") (pinfunction "2_2") (pintype "bidirectional"))
    )
    (net (code "95") (name "PC_12") (class "Default")
      (node (ref "Q8") (pin "1") (pinfunction "G_1") (pintype "passive"))
      (node (ref "R11") (pin "1") (pinfunction "1_1") (pintype "passive"))
      (node (ref "R28") (pin "2") (pinfunction "2_2") (pintype "passive"))
      (node (ref "U4") (pin "53") (pinfunction "PC12_53") (pintype "bidirectional"))
      (node (ref "X52") (pin "9") (pinfunction "9_9") (pintype "passive"))
      (node (ref "X8") (pin "12") (pinfunction "12_12") (pintype "bidirectional"))
    )
    (net (code "96") (name "PC_13") (class "Default")
      (node (ref "Q10") (pin "1") (pinfunction "G_1") (pintype "passive"))
      (node (ref "R12") (pin "1") (pinfunction "1_1") (pintype "passive"))
      (node (ref "R30") (pin "2") (pinfunction "2_2") (pintype "passive"))
      (node (ref "U4") (pin "2") (pinfunction "PC13_2") (pintype "bidirectional"))
      (node (ref "X52") (pin "10") (pinfunction "10_10") (pintype "passive"))
      (node (ref "X6") (pin "5") (pinfunction "5_5") (pintype "bidirectional"))
    )
    (net (code "97") (name "PD_2") (class "Default")
      (node (ref "U3") (pin "2") (pinfunction "~{RE}_2") (pintype "bidirectional"))
      (node (ref "U3") (pin "3") (pinfunction "DE_3") (pintype "bidirectional"))
      (node (ref "U4") (pin "54") (pinfunction "PD2_54") (pintype "bidirectional"))
      (node (ref "X8") (pin "3") (pinfunction "3_3") (pintype "bidirectional"))
    )
    (net (code "98") (name "SPI1_MISO") (class "Default")
      (node (ref "U4") (pin "22") (pinfunction "PA6_22") (pintype "bidirectional"))
      (node (ref "X25") (pin "3") (pinfunction "3_3") (pintype "passive"))
      (node (ref "X31") (pin "3") (pinfunction "3_3") (pintype "passive"))
      (node (ref "X39") (pin "3") (pinfunction "3_3") (pintype "passive"))
      (node (ref "X45") (pin "3") (pinfunction "3_3") (pintype "passive"))
      (node (ref "X7") (pin "11") (pinfunction "11_11") (pintype "bidirectional"))
    )
    (net (code "99") (name "SPI1_MOSI") (class "Default")
      (node (ref "U4") (pin "23") (pinfunction "PA7_23") (pintype "bidirectional"))
      (node (ref "X25") (pin "2") (pinfunction "2_2") (pintype "passive"))
      (node (ref "X31") (pin "2") (pinfunction "2_2") (pintype "passive"))
      (node (ref "X39") (pin "2") (pinfunction "2_2") (pintype "passive"))
      (node (ref "X45") (pin "2") (pinfunction "2_2") (pintype "passive"))
      (node (ref "X7") (pin "4") (pinfunction "4_4") (pintype "bidirectional"))
    )
    (net (code "100") (name "SPI1_SCK") (class "Default")
      (node (ref "U4") (pin "21") (pinfunction "PA5_21") (pintype "bidirectional"))
      (node (ref "X25") (pin "1") (pinfunction "1_1") (pintype "passive"))
      (node (ref "X31") (pin "1") (pinfunction "1_1") (pintype "passive"))
      (node (ref "X39") (pin "1") (pinfunction "1_1") (pintype "passive"))
      (node (ref "X45") (pin "1") (pinfunction "1_1") (pintype "passive"))
      (node (ref "X7") (pin "5") (pinfunction "5_5") (pintype "bidirectional"))
    )
    (net (code "101") (name "SPI2_MISO") (class "Default")
      (node (ref "U4") (pin "35") (pinfunction "PB14_35") (pintype "bidirectional"))
      (node (ref "U5") (pin "P7") (pinfunction "DOUT_P7") (pintype "bidirectional"))
      (node (ref "X9") (pin "9") (pinfunction "9_9") (pintype "bidirectional"))
    )
    (net (code "102") (name "SPI2_MOSI") (class "Default")
      (node (ref "U4") (pin "36") (pinfunction "PB15_36") (pintype "bidirectional"))
      (node (ref "U5") (pin "P6") (pinfunction "DIN_P6") (pintype "bidirectional"))
      (node (ref "X9") (pin "6") (pinfunction "6_6") (pintype "bidirectional"))
    )
    (net (code "103") (name "SPI2_SCK") (class "Default")
      (node (ref "U4") (pin "34") (pinfunction "PB13_34") (pintype "bidirectional"))
      (node (ref "U5") (pin "P5") (pinfunction "SCK_P5") (pintype "bidirectional"))
      (node (ref "X9") (pin "7") (pinfunction "7_7") (pintype "bidirectional"))
    )
    (net (code "104") (name "SWD_CLK") (class "Default")
      (node (ref "U4") (pin "49") (pinfunction "PA14_49") (pintype "bidirectional"))
      (node (ref "X3") (pin "4") (pinfunction "SWDCLK_4") (pintype "bidirectional"))
      (node (ref "X8") (pin "14") (pinfunction "14_14") (pintype "bidirectional"))
    )
    (net (code "105") (name "SWD_IO") (class "Default")
      (node (ref "U4") (pin "46") (pinfunction "PA13_46") (pintype "bidirectional"))
      (node (ref "X3") (pin "2") (pinfunction "SWDIO_2") (pintype "bidirectional"))
      (node (ref "X9") (pin "14") (pinfunction "14_14") (pintype "bidirectional"))
    )
    (net (code "106") (name "SWO") (class "Default")
      (node (ref "U4") (pin "55") (pinfunction "PB3_55") (pintype "bidirectional"))
      (node (ref "X3") (pin "6") (pinfunction "SWO_6") (pintype "bidirectional"))
      (node (ref "X8") (pin "11") (pinfunction "11_11") (pintype "bidirectional"))
    )
    (net (code "107") (name "USART1_CTS") (class "Default")
      (node (ref "U4") (pin "44") (pinfunction "PA11_44") (pintype "bidirectional"))
      (node (ref "U5") (pin "P44") (pinfunction "UART_RTS_P44") (pintype "bidirectional"))
      (node (ref "X9") (pin "2") (pinfunction "2_2") (pintype "bidirectional"))
    )
    (net (code "108") (name "USART1_RTS") (class "Default")
      (node (ref "U4") (pin "45") (pinfunction "PA12_45") (pintype "bidirectional"))
      (node (ref "U5") (pin "P51") (pinfunction "UART_CTS_P51") (pintype "bidirectional"))
      (node (ref "X9") (pin "1") (pinfunction "1_1") (pintype "bidirectional"))
    )
    (net (code "109") (name "USART1_RX") (class "Default")
      (node (ref "U4") (pin "43") (pinfunction "PA10_43") (pintype "bidirectional"))
      (node (ref "U5") (pin "P46") (pinfunction "UART_TX_P46") (pintype "bidirectional"))
      (node (ref "X9") (pin "13") (pinfunction "13_13") (pintype "bidirectional"))
    )
    (net (code "110") (name "USART1_TX") (class "Default")
      (node (ref "U4") (pin "42") (pinfunction "PA9_42") (pintype "bidirectional"))
      (node (ref "U5") (pin "P47") (pinfunction "UART_RX_P47") (pintype "bidirectional"))
      (node (ref "X9") (pin "3") (pinfunction "3_3") (pintype "bidirectional"))
    )
    (net (code "111") (name "USART2_CTS") (class "Default")
      (node (ref "U4") (pin "14") (pinfunction "PA0-WKUP_14") (pintype "bidirectional"))
      (node (ref "X16") (pin "2") (pinfunction "2_2") (pintype "passive"))
      (node (ref "X6") (pin "10") (pinfunction "10_10") (pintype "bidirectional"))
    )
    (net (code "112") (name "USART2_RTS") (class "Default")
      (node (ref "U4") (pin "15") (pinfunction "PA1_15") (pintype "bidirectional"))
      (node (ref "X16") (pin "1") (pinfunction "1_1") (pintype "passive"))
      (node (ref "X6") (pin "4") (pinfunction "4_4") (pintype "bidirectional"))
    )
    (net (code "113") (name "USART2_RX") (class "Default")
      (node (ref "U4") (pin "17") (pinfunction "PA3_17") (pintype "bidirectional"))
      (node (ref "X16") (pin "3") (pinfunction "3_3") (pintype "passive"))
      (node (ref "X7") (pin "6") (pinfunction "6_6") (pintype "bidirectional"))
    )
    (net (code "114") (name "USART2_TX") (class "Default")
      (node (ref "U4") (pin "16") (pinfunction "PA2_16") (pintype "bidirectional"))
      (node (ref "X16") (pin "4") (pinfunction "4_4") (pintype "passive"))
      (node (ref "X6") (pin "11") (pinfunction "11_11") (pintype "bidirectional"))
    )
    (net (code "115") (name "USART3_RX") (class "Default")
      (node (ref "U3") (pin "1") (pinfunction "R_1") (pintype "bidirectional"))
      (node (ref "U4") (pin "25") (pinfunction "PC5_25") (pintype "bidirectional"))
      (node (ref "X7") (pin "3") (pinfunction "3_3") (pintype "bidirectional"))
    )
    (net (code "116") (name "USART3_TX") (class "Default")
      (node (ref "U3") (pin "4") (pinfunction "D_4") (pintype "bidirectional"))
      (node (ref "U4") (pin "51") (pinfunction "PC10_51") (pintype "bidirectional"))
      (node (ref "X8") (pin "13") (pinfunction "13_13") (pintype "bidirectional"))
    )
    (net (code "117") (name "VBAT") (class "Default")
      (node (ref "C23") (pin "1") (pinfunction "1_1") (pintype "passive"))
      (node (ref "D6") (pin "-") (pinfunction "-_-") (pintype "passive"))
      (node (ref "D7") (pin "-") (pinfunction "-_-") (pintype "passive"))
      (node (ref "U4") (pin "1") (pinfunction "VBAT_1") (pintype "power_in"))
      (node (ref "X6") (pin "14") (pinfunction "14_14") (pintype "bidirectional"))
    )
    (net (code "118") (name "VDDA") (class "Default")
      (node (ref "C17") (pin "1") (pinfunction "1_1") (pintype "passive"))
      (node (ref "L3") (pin "1") (pinfunction "1_1") (pintype "passive"))
      (node (ref "U4") (pin "13") (pinfunction "VDDA_13") (pintype "power_in"))
    )
    (net (code "119") (name "unconnected-(U5-FORCE_AP-PadP10)") (class "Default")
      (node (ref "U5") (pin "P10") (pinfunction "FORCE_AP_P10") (pintype "bidirectional"))
    )
    (net (code "120") (name "unconnected-(U5-NC1-PadP3)") (class "Default")
      (node (ref "U5") (pin "P3") (pinfunction "NC1_P3") (pintype "bidirectional"))
    )
    (net (code "121") (name "unconnected-(U5-NC2-PadP9)") (class "Default")
      (node (ref "U5") (pin "P9") (pinfunction "NC2_P9") (pintype "bidirectional"))
    )
    (net (code "122") (name "unconnected-(U5-NC3-PadP12)") (class "Default")
      (node (ref "U5") (pin "P12") (pinfunction "NC3_P12") (pintype "bidirectional"))
    )
    (net (code "123") (name "unconnected-(U5-NC4-PadP13)") (class "Default")
      (node (ref "U5") (pin "P13") (pinfunction "NC4_P13") (pintype "bidirectional"))
    )
    (net (code "124") (name "unconnected-(U5-NC5-PadP14)") (class "Default")
      (node (ref "U5") (pin "P14") (pinfunction "NC5_P14") (pintype "bidirectional"))
    )
    (net (code "125") (name "unconnected-(U5-NC6-PadP15)") (class "Default")
      (node (ref "U5") (pin "P15") (pinfunction "NC6_P15") (pintype "bidirectional"))
    )
    (net (code "126") (name "unconnected-(U5-NC7-PadP17)") (class "Default")
      (node (ref "U5") (pin "P17") (pinfunction "NC7_P17") (pintype "bidirectional"))
    )
    (net (code "127") (name "unconnected-(U5-NC8-PadP18)") (class "Default")
      (node (ref "U5") (pin "P18") (pinfunction "NC8_P18") (pintype "bidirectional"))
    )
    (net (code "128") (name "unconnected-(U5-NC9-PadP20)") (class "Default")
      (node (ref "U5") (pin "P20") (pinfunction "NC9_P20") (pintype "bidirectional"))
    )
    (net (code "129") (name "unconnected-(U5-NC10-PadP22)") (class "Default")
      (node (ref "U5") (pin "P22") (pinfunction "NC10_P22") (pintype "bidirectional"))
    )
    (net (code "130") (name "unconnected-(U5-NC11-PadP25)") (class "Default")
      (node (ref "U5") (pin "P25") (pinfunction "NC11_P25") (pintype "bidirectional"))
    )
    (net (code "131") (name "unconnected-(U5-NC12-PadP26)") (class "Default")
      (node (ref "U5") (pin "P26") (pinfunction "NC12_P26") (pintype "bidirectional"))
    )
    (net (code "132") (name "unconnected-(U5-NC13-PadP29)") (class "Default")
      (node (ref "U5") (pin "P29") (pinfunction "NC13_P29") (pintype "bidirectional"))
    )
    (net (code "133") (name "unconnected-(U5-NC14-PadP33)") (class "Default")
      (node (ref "U5") (pin "P33") (pinfunction "NC14_P33") (pintype "bidirectional"))
    )
    (net (code "134") (name "unconnected-(U5-NC15-PadP39)") (class "Default")
      (node (ref "U5") (pin "P39") (pinfunction "NC15_P39") (pintype "bidirectional"))
    )
    (net (code "135") (name "unconnected-(U5-NC16-PadP41)") (class "Default")
      (node (ref "U5") (pin "P41") (pinfunction "NC16_P41") (pintype "bidirectional"))
    )
    (net (code "136") (name "unconnected-(U5-NC17-PadP42)") (class "Default")
      (node (ref "U5") (pin "P42") (pinfunction "NC17_P42") (pintype "bidirectional"))
    )
    (net (code "137") (name "unconnected-(U5-NC18-PadP45)") (class "Default")
      (node (ref "U5") (pin "P45") (pinfunction "NC18_P45") (pintype "bidirectional"))
    )
    (net (code "138") (name "unconnected-(U5-NC19-PadP53)") (class "Default")
      (node (ref "U5") (pin "P53") (pinfunction "NC19_P53") (pintype "bidirectional"))
    )
    (net (code "139") (name "unconnected-(U5-NC20-PadP54)") (class "Default")
      (node (ref "U5") (pin "P54") (pinfunction "NC20_P54") (pintype "bidirectional"))
    )
    (net (code "140") (name "unconnected-(U5-RES1-PadP19)") (class "Default")
      (node (ref "U5") (pin "P19") (pinfunction "RES1_P19") (pintype "bidirectional"))
    )
    (net (code "141") (name "unconnected-(U5-SOP0-PadP34)") (class "Default")
      (node (ref "U5") (pin "P34") (pinfunction "SOP0_P34") (pintype "bidirectional"))
    )
    (net (code "142") (name "unconnected-(U5-SOP1-PadP24)") (class "Default")
      (node (ref "U5") (pin "P24") (pinfunction "SOP1_P24") (pintype "bidirectional"))
    )
    (net (code "143") (name "unconnected-(U5-~{RESET}-PadP35)") (class "Default")
      (node (ref "U5") (pin "P35") (pinfunction "~{RESET}_P35") (pintype "bidirectional"))
    )
    (net (code "144") (name "unconnected-(X3-TDI-Pad8)") (class "Default")
      (node (ref "X3") (pin "8") (pinfunction "TDI_8") (pintype "bidirectional"))
    )
    (net (code "145") (name "~{RESET}") (class "Default")
      (node (ref "R33") (pin "2") (pinfunction "2_2") (pintype "passive"))
      (node (ref "SW1") (pin "P$1") (pinfunction "1_P$1") (pintype "passive"))
      (node (ref "U4") (pin "7") (pinfunction "NRST_7") (pintype "bidirectional"))
      (node (ref "X3") (pin "10") (pinfunction "NRESET_10") (pintype "bidirectional"))
      (node (ref "X6") (pin "1") (pinfunction "1_1") (pintype "bidirectional"))
    )
  )
)
